# Sheet1.net
KiCad netlist of a schematic drawn in Altium Designer
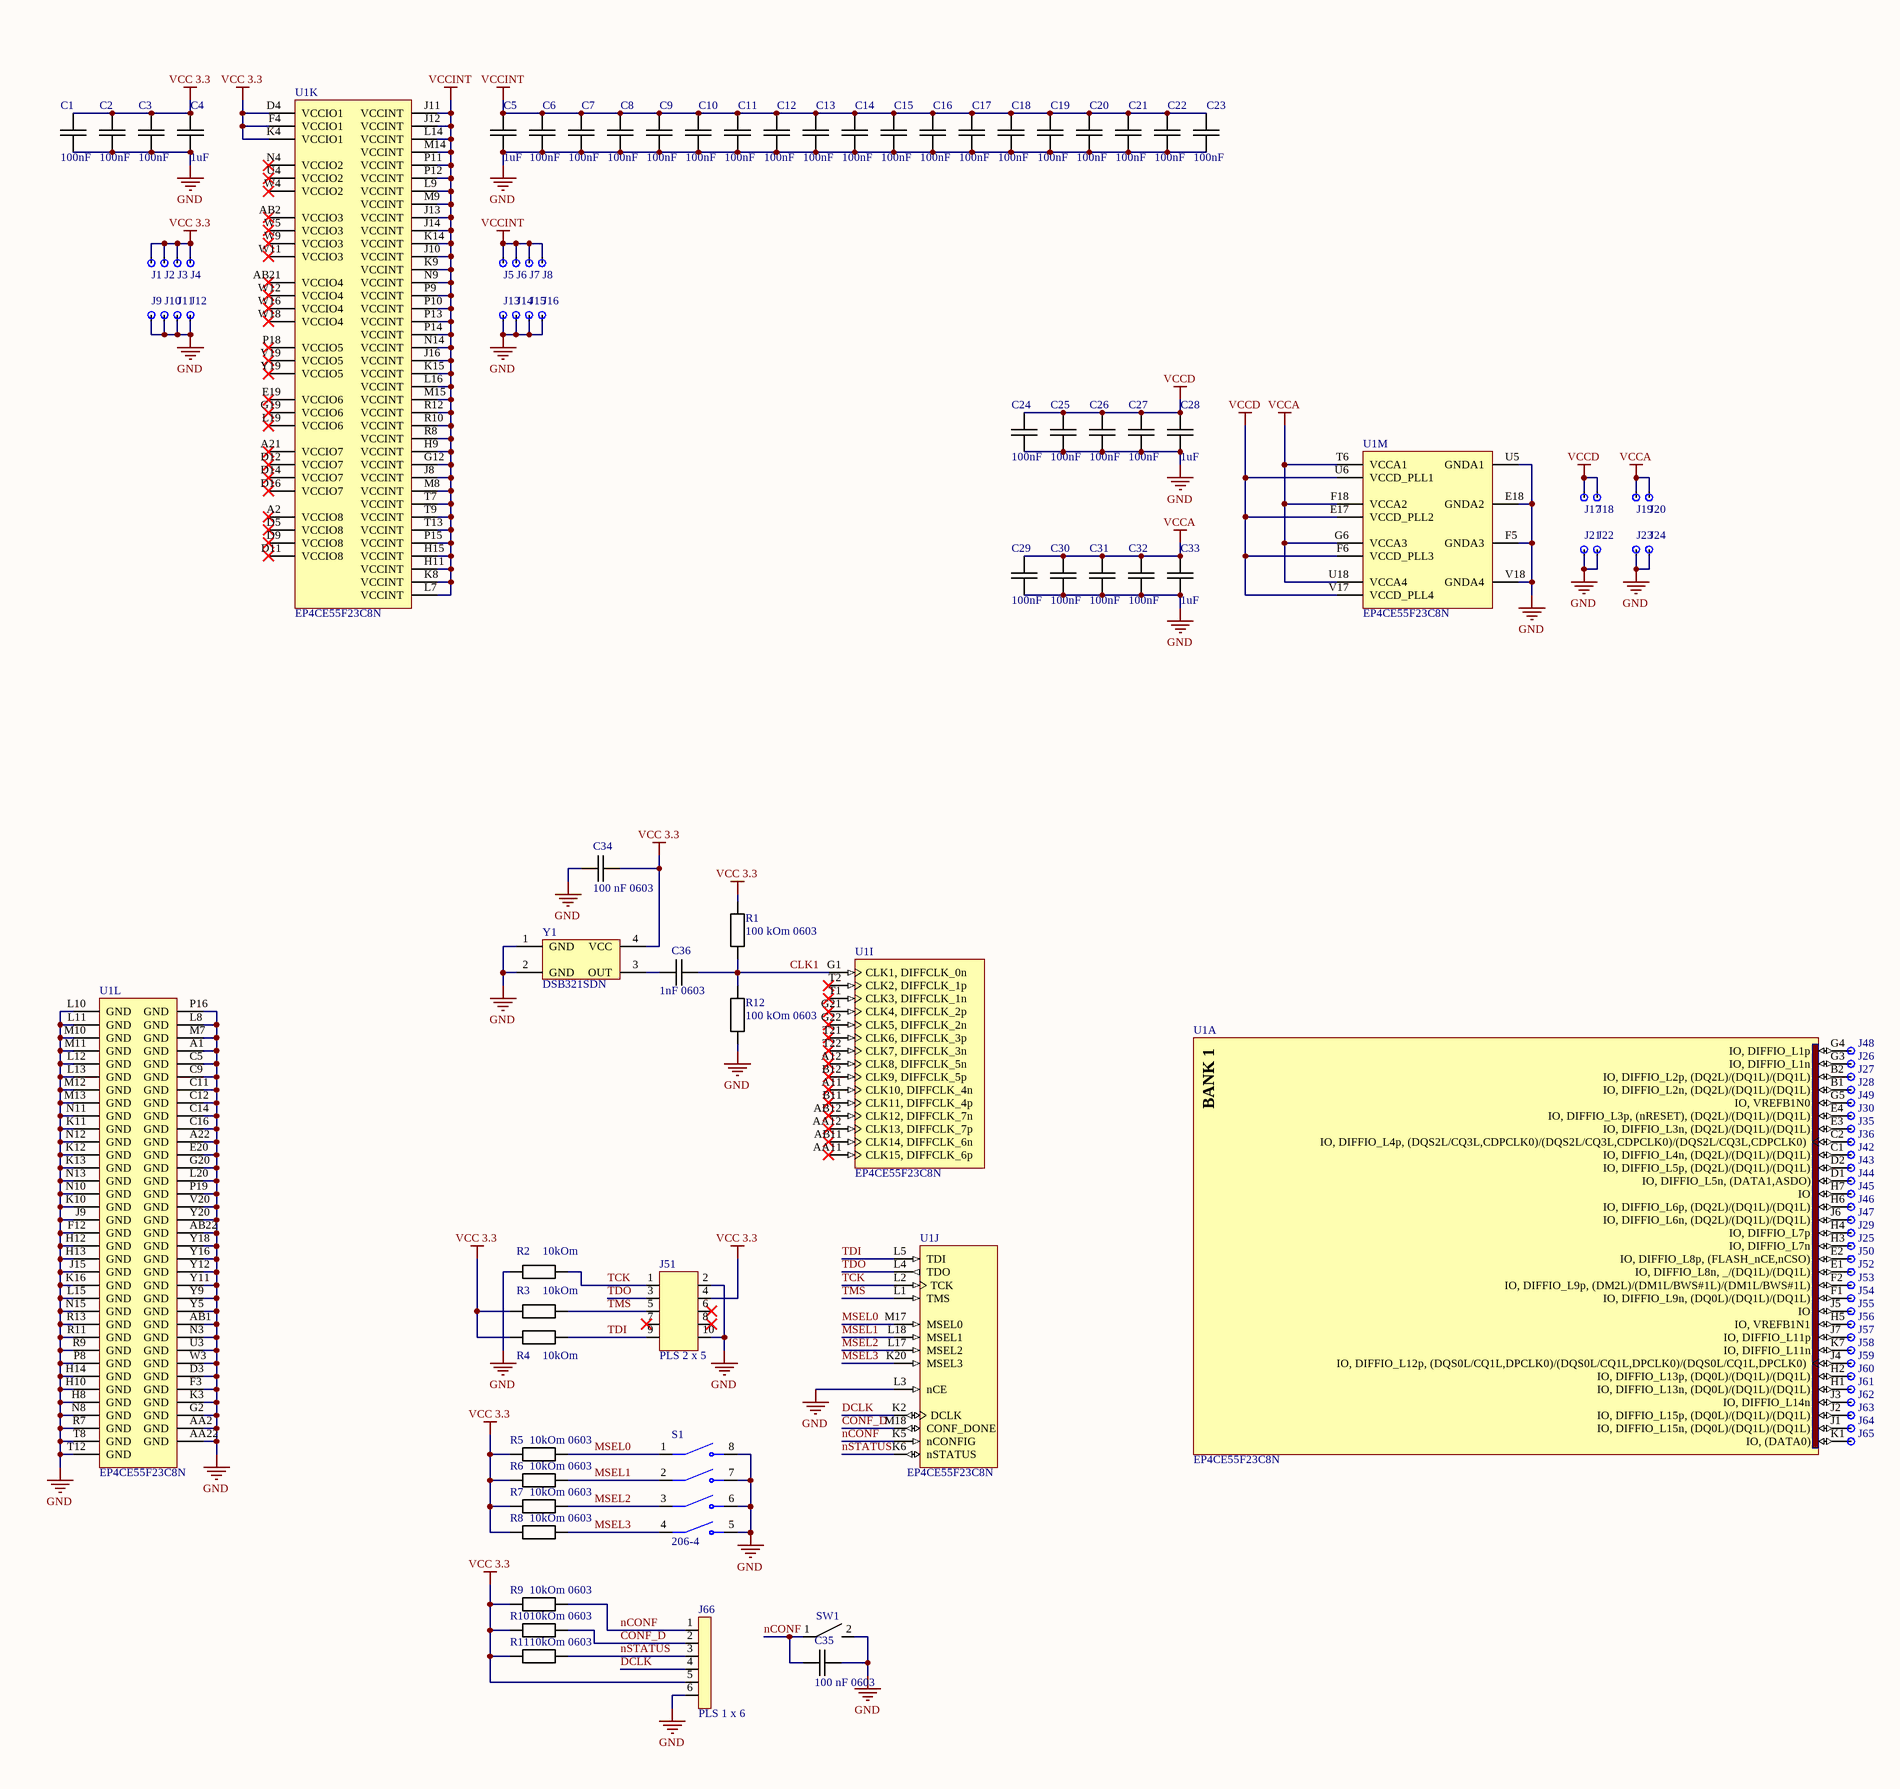
[diagram p0: Sheet1.SchDoc, left]
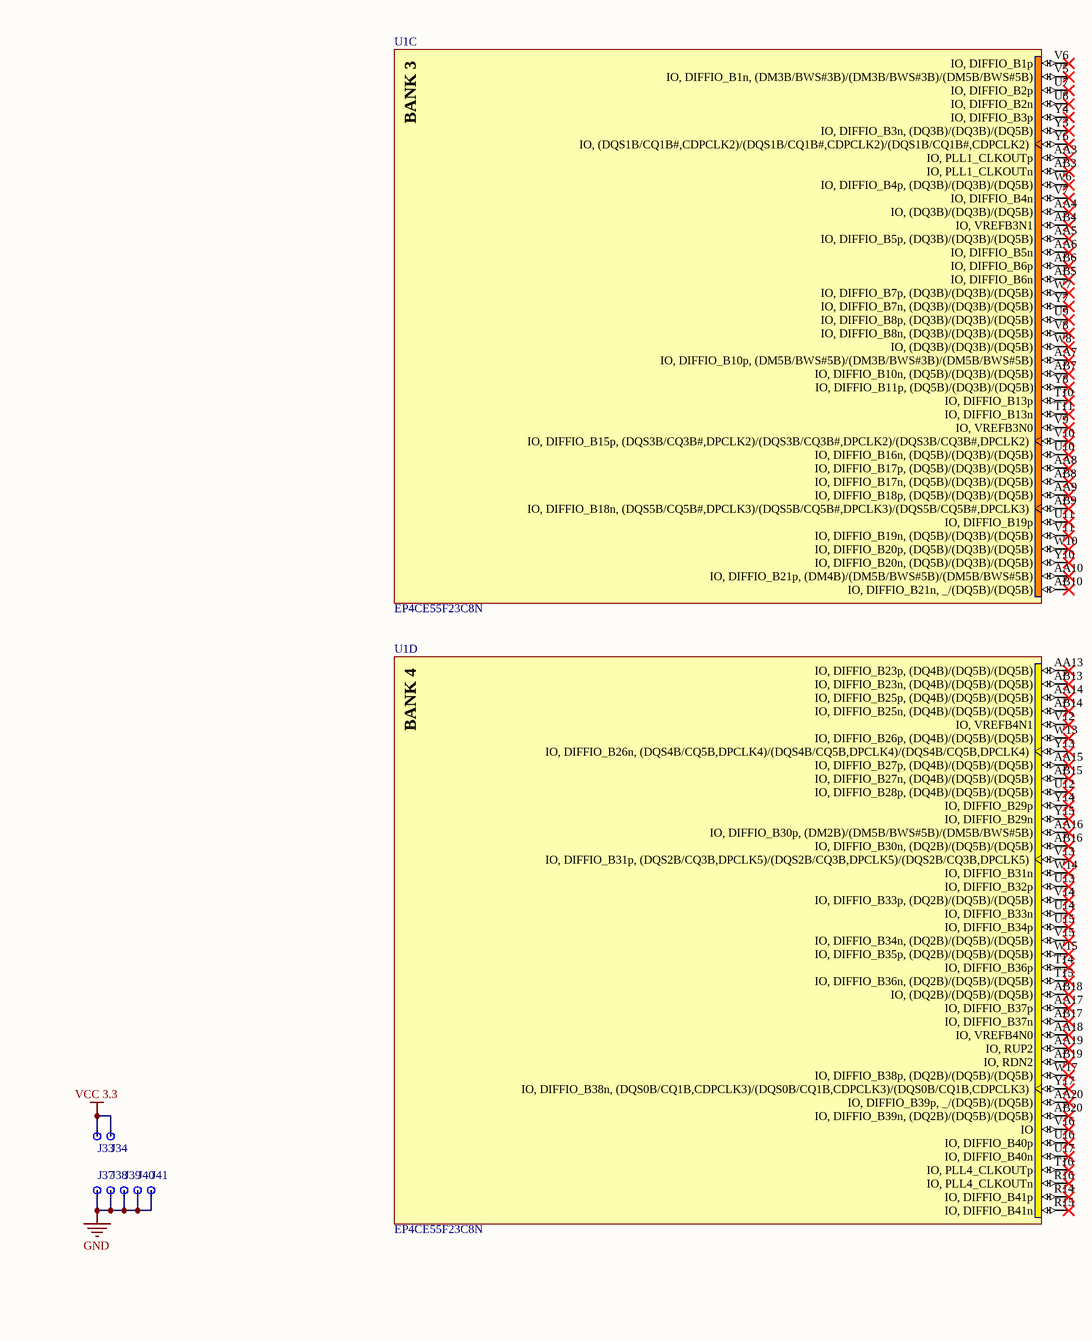
[diagram p1: Sheet1.SchDoc, middle]
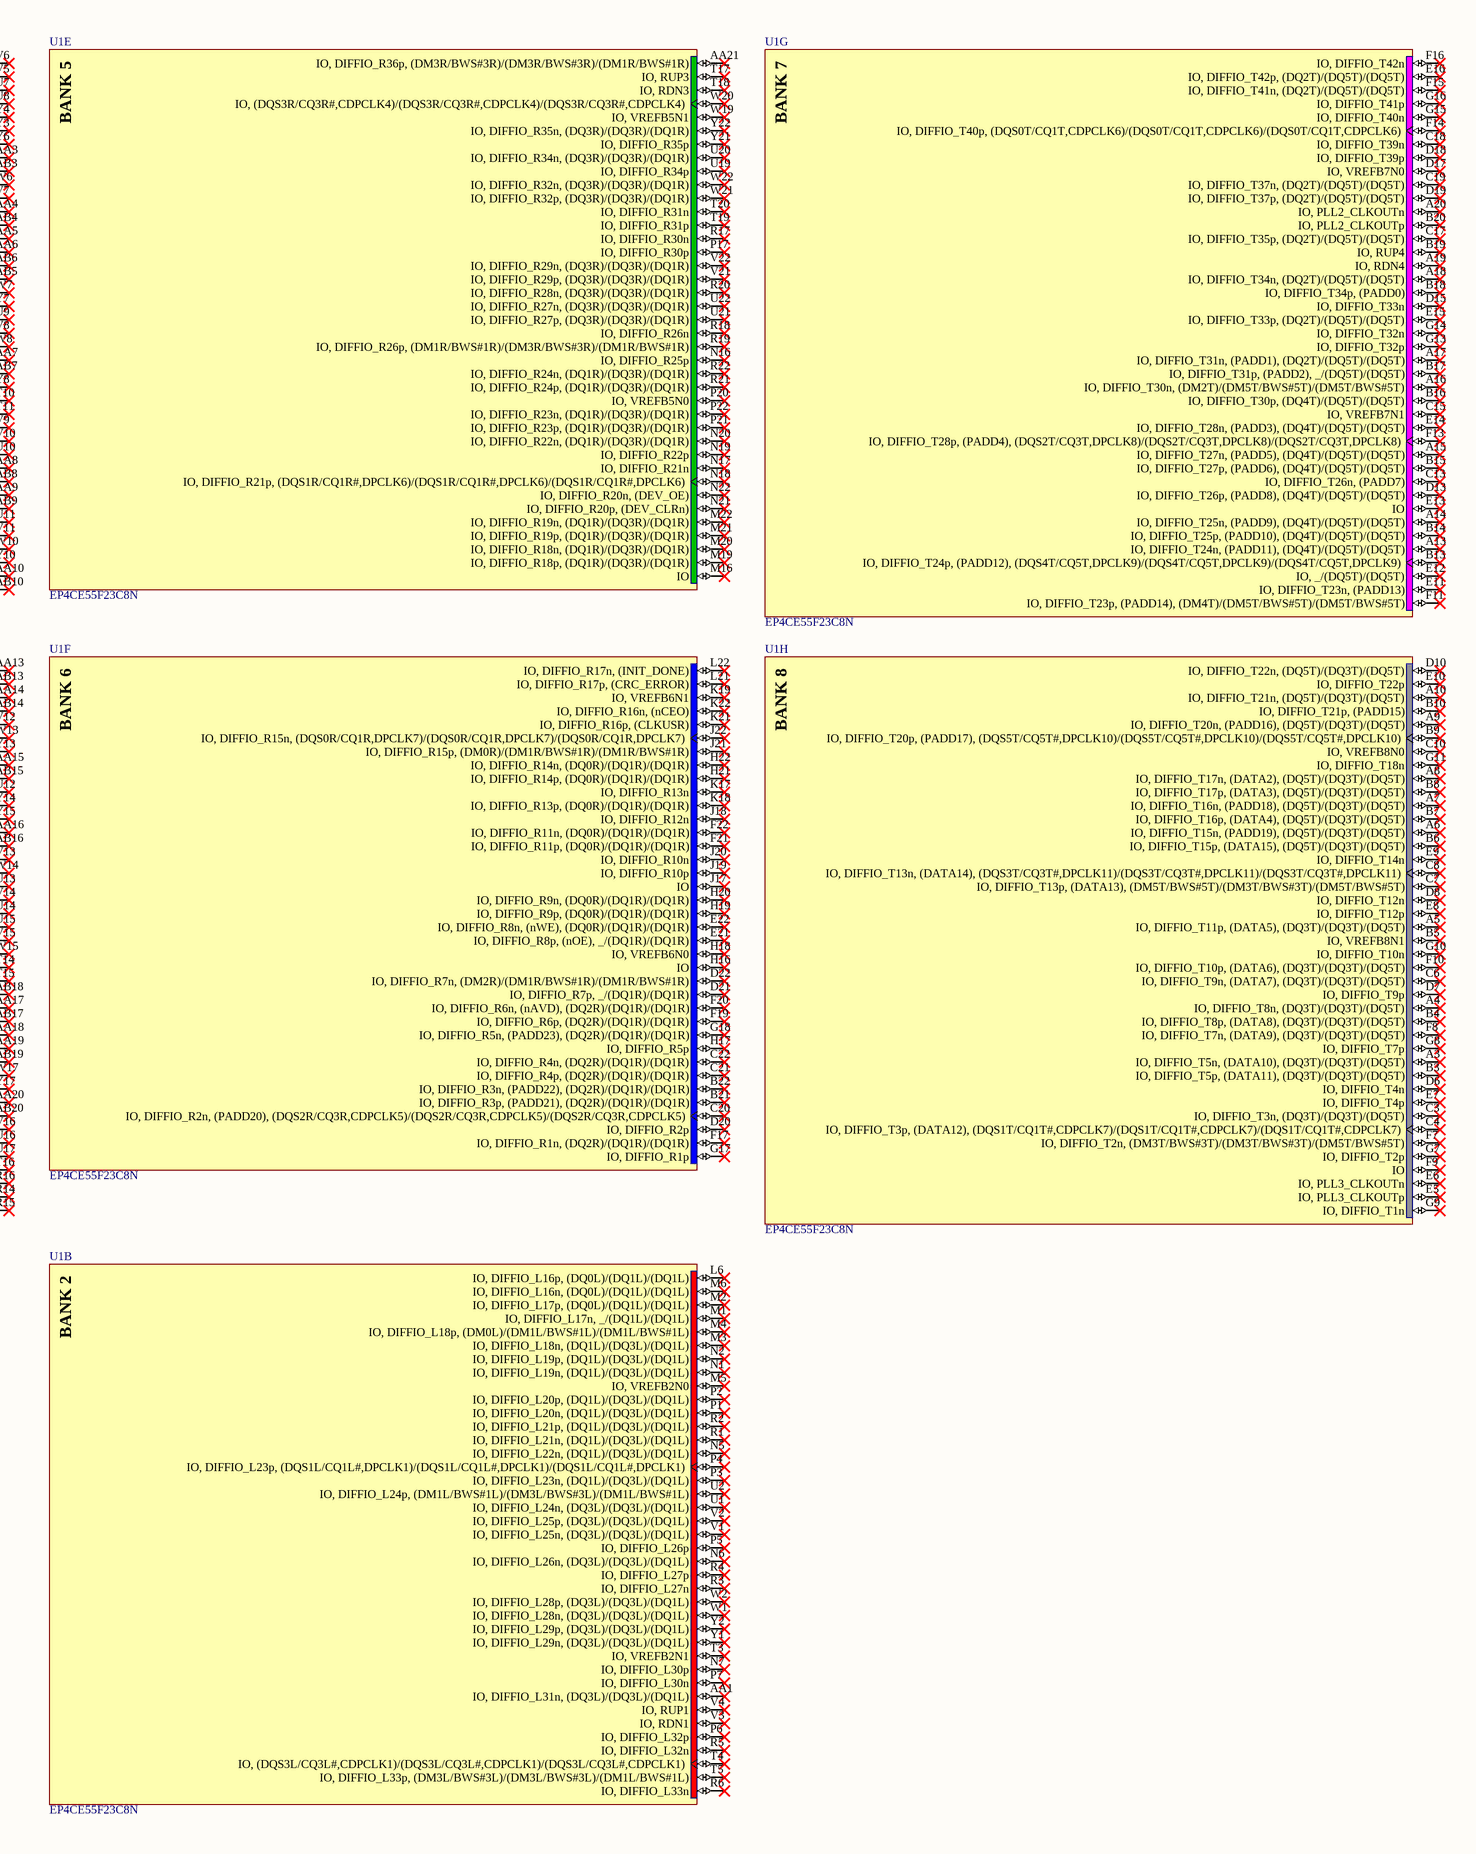
[diagram p2: Sheet1.SchDoc, right]

(export (version "E")
  (design (tool "Eeschema 10.0.6"))
  (components
    (comp (ref "C1")
      (value "100nF")
      (footprint "CAPC1608X90")
      (libsource (lib "Schlib1") (part "100 nF 0603"))
    )
    (comp (ref "C2")
      (value "100nF")
      (footprint "CAPC1608X90")
      (libsource (lib "Schlib1") (part "100 nF 0603"))
    )
    (comp (ref "C3")
      (value "100nF")
      (footprint "CAPC1608X90")
      (libsource (lib "Schlib1") (part "100 nF 0603"))
    )
    (comp (ref "C4") (value "1uF") (footprint "CAPC1608X90") (libsource (lib "Schlib1") (part "1uF 0603")))
    (comp (ref "C5") (value "1uF") (footprint "CAPC1608X90") (libsource (lib "Schlib1") (part "1uF 0603")))
    (comp (ref "C6")
      (value "100nF")
      (footprint "CAPC1608X90")
      (libsource (lib "Schlib1") (part "100 nF 0603"))
    )
    (comp (ref "C7")
      (value "100nF")
      (footprint "CAPC1608X90")
      (libsource (lib "Schlib1") (part "100 nF 0603"))
    )
    (comp (ref "C8")
      (value "100nF")
      (footprint "CAPC1608X90")
      (libsource (lib "Schlib1") (part "100 nF 0603"))
    )
    (comp (ref "C9")
      (value "100nF")
      (footprint "CAPC1608X90")
      (libsource (lib "Schlib1") (part "100 nF 0603"))
    )
    (comp (ref "C10")
      (value "100nF")
      (footprint "CAPC1608X90")
      (libsource (lib "Schlib1") (part "100 nF 0603"))
    )
    (comp (ref "C11")
      (value "100nF")
      (footprint "CAPC1608X90")
      (libsource (lib "Schlib1") (part "100 nF 0603"))
    )
    (comp (ref "C12")
      (value "100nF")
      (footprint "CAPC1608X90")
      (libsource (lib "Schlib1") (part "100 nF 0603"))
    )
    (comp (ref "C13")
      (value "100nF")
      (footprint "CAPC1608X90")
      (libsource (lib "Schlib1") (part "100 nF 0603"))
    )
    (comp (ref "C14")
      (value "100nF")
      (footprint "CAPC1608X90")
      (libsource (lib "Schlib1") (part "100 nF 0603"))
    )
    (comp (ref "C15")
      (value "100nF")
      (footprint "CAPC1608X90")
      (libsource (lib "Schlib1") (part "100 nF 0603"))
    )
    (comp (ref "C16")
      (value "100nF")
      (footprint "CAPC1608X90")
      (libsource (lib "Schlib1") (part "100 nF 0603"))
    )
    (comp (ref "C17")
      (value "100nF")
      (footprint "CAPC1608X90")
      (libsource (lib "Schlib1") (part "100 nF 0603"))
    )
    (comp (ref "C18")
      (value "100nF")
      (footprint "CAPC1608X90")
      (libsource (lib "Schlib1") (part "100 nF 0603"))
    )
    (comp (ref "C19")
      (value "100nF")
      (footprint "CAPC1608X90")
      (libsource (lib "Schlib1") (part "100 nF 0603"))
    )
    (comp (ref "C20")
      (value "100nF")
      (footprint "CAPC1608X90")
      (libsource (lib "Schlib1") (part "100 nF 0603"))
    )
    (comp (ref "C21")
      (value "100nF")
      (footprint "CAPC1608X90")
      (libsource (lib "Schlib1") (part "100 nF 0603"))
    )
    (comp (ref "C22")
      (value "100nF")
      (footprint "CAPC1608X90")
      (libsource (lib "Schlib1") (part "100 nF 0603"))
    )
    (comp (ref "C23")
      (value "100nF")
      (footprint "CAPC1608X90")
      (libsource (lib "Schlib1") (part "100 nF 0603"))
    )
    (comp (ref "C24")
      (value "100nF")
      (footprint "CAPC1608X90")
      (libsource (lib "Schlib1") (part "100 nF 0603"))
    )
    (comp (ref "C25")
      (value "100nF")
      (footprint "CAPC1608X90")
      (libsource (lib "Schlib1") (part "100 nF 0603"))
    )
    (comp (ref "C26")
      (value "100nF")
      (footprint "CAPC1608X90")
      (libsource (lib "Schlib1") (part "100 nF 0603"))
    )
    (comp (ref "C27")
      (value "100nF")
      (footprint "CAPC1608X90")
      (libsource (lib "Schlib1") (part "100 nF 0603"))
    )
    (comp (ref "C28") (value "1uF") (footprint "CAPC1608X90") (libsource (lib "Schlib1") (part "1uF 0603")))
    (comp (ref "C29")
      (value "100nF")
      (footprint "CAPC1608X90")
      (libsource (lib "Schlib1") (part "100 nF 0603"))
    )
    (comp (ref "C30")
      (value "100nF")
      (footprint "CAPC1608X90")
      (libsource (lib "Schlib1") (part "100 nF 0603"))
    )
    (comp (ref "C31")
      (value "100nF")
      (footprint "CAPC1608X90")
      (libsource (lib "Schlib1") (part "100 nF 0603"))
    )
    (comp (ref "C32")
      (value "100nF")
      (footprint "CAPC1608X90")
      (libsource (lib "Schlib1") (part "100 nF 0603"))
    )
    (comp (ref "C33") (value "1uF") (footprint "CAPC1608X90") (libsource (lib "Schlib1") (part "1uF 0603")))
    (comp (ref "C34")
      (value "100 nF 0603")
      (footprint "CAPC1608X90")
      (libsource (lib "Schlib1") (part "100 nF 0603"))
    )
    (comp (ref "C35")
      (value "100 nF 0603")
      (footprint "CAPC1608X90")
      (libsource (lib "Schlib1") (part "100 nF 0603"))
    )
    (comp (ref "C36")
      (value "1nF 0603")
      (footprint "CAPC1608X90")
      (libsource (lib "Schlib1") (part "1nF 0603"))
    )
    (comp (ref "J1") (value "Pin1") (footprint "Pin1") (libsource (lib "Schlib1") (part "Pin1")))
    (comp (ref "J2") (value "Pin1") (footprint "Pin1") (libsource (lib "Schlib1") (part "Pin1")))
    (comp (ref "J3") (value "Pin1") (footprint "Pin1") (libsource (lib "Schlib1") (part "Pin1")))
    (comp (ref "J4") (value "Pin1") (footprint "Pin1") (libsource (lib "Schlib1") (part "Pin1")))
    (comp (ref "J5") (value "Pin1") (footprint "Pin1") (libsource (lib "Schlib1") (part "Pin1")))
    (comp (ref "J6") (value "Pin1") (footprint "Pin1") (libsource (lib "Schlib1") (part "Pin1")))
    (comp (ref "J7") (value "Pin1") (footprint "Pin1") (libsource (lib "Schlib1") (part "Pin1")))
    (comp (ref "J8") (value "Pin1") (footprint "Pin1") (libsource (lib "Schlib1") (part "Pin1")))
    (comp (ref "J9") (value "Pin1") (footprint "Pin1") (libsource (lib "Schlib1") (part "Pin1")))
    (comp (ref "J10") (value "Pin1") (footprint "Pin1") (libsource (lib "Schlib1") (part "Pin1")))
    (comp (ref "J11") (value "Pin1") (footprint "Pin1") (libsource (lib "Schlib1") (part "Pin1")))
    (comp (ref "J12") (value "Pin1") (footprint "Pin1") (libsource (lib "Schlib1") (part "Pin1")))
    (comp (ref "J13") (value "Pin1") (footprint "Pin1") (libsource (lib "Schlib1") (part "Pin1")))
    (comp (ref "J14") (value "Pin1") (footprint "Pin1") (libsource (lib "Schlib1") (part "Pin1")))
    (comp (ref "J15") (value "Pin1") (footprint "Pin1") (libsource (lib "Schlib1") (part "Pin1")))
    (comp (ref "J16") (value "Pin1") (footprint "Pin1") (libsource (lib "Schlib1") (part "Pin1")))
    (comp (ref "J17") (value "Pin1") (footprint "Pin1") (libsource (lib "Schlib1") (part "Pin1")))
    (comp (ref "J18") (value "Pin1") (footprint "Pin1") (libsource (lib "Schlib1") (part "Pin1")))
    (comp (ref "J19") (value "Pin1") (footprint "Pin1") (libsource (lib "Schlib1") (part "Pin1")))
    (comp (ref "J20") (value "Pin1") (footprint "Pin1") (libsource (lib "Schlib1") (part "Pin1")))
    (comp (ref "J21") (value "Pin1") (footprint "Pin1") (libsource (lib "Schlib1") (part "Pin1")))
    (comp (ref "J22") (value "Pin1") (footprint "Pin1") (libsource (lib "Schlib1") (part "Pin1")))
    (comp (ref "J23") (value "Pin1") (footprint "Pin1") (libsource (lib "Schlib1") (part "Pin1")))
    (comp (ref "J24") (value "Pin1") (footprint "Pin1") (libsource (lib "Schlib1") (part "Pin1")))
    (comp (ref "J25") (value "Pin1") (footprint "Pin1") (libsource (lib "Schlib1") (part "Pin1")))
    (comp (ref "J26") (value "Pin1") (footprint "Pin1") (libsource (lib "Schlib1") (part "Pin1")))
    (comp (ref "J27") (value "Pin1") (footprint "Pin1") (libsource (lib "Schlib1") (part "Pin1")))
    (comp (ref "J28") (value "Pin1") (footprint "Pin1") (libsource (lib "Schlib1") (part "Pin1")))
    (comp (ref "J29") (value "Pin1") (footprint "Pin1") (libsource (lib "Schlib1") (part "Pin1")))
    (comp (ref "J30") (value "Pin1") (footprint "Pin1") (libsource (lib "Schlib1") (part "Pin1")))
    (comp (ref "J33") (value "Pin1") (footprint "Pin1") (libsource (lib "Schlib1") (part "Pin1")))
    (comp (ref "J34") (value "Pin1") (footprint "Pin1") (libsource (lib "Schlib1") (part "Pin1")))
    (comp (ref "J35") (value "Pin1") (footprint "Pin1") (libsource (lib "Schlib1") (part "Pin1")))
    (comp (ref "J36") (value "Pin1") (footprint "Pin1") (libsource (lib "Schlib1") (part "Pin1")))
    (comp (ref "J37") (value "Pin1") (footprint "Pin1") (libsource (lib "Schlib1") (part "Pin1")))
    (comp (ref "J38") (value "Pin1") (footprint "Pin1") (libsource (lib "Schlib1") (part "Pin1")))
    (comp (ref "J39") (value "Pin1") (footprint "Pin1") (libsource (lib "Schlib1") (part "Pin1")))
    (comp (ref "J40") (value "Pin1") (footprint "Pin1") (libsource (lib "Schlib1") (part "Pin1")))
    (comp (ref "J41") (value "Pin1") (footprint "Pin1") (libsource (lib "Schlib1") (part "Pin1")))
    (comp (ref "J42") (value "Pin1") (footprint "Pin1") (libsource (lib "Schlib1") (part "Pin1")))
    (comp (ref "J43") (value "Pin1") (footprint "Pin1") (libsource (lib "Schlib1") (part "Pin1")))
    (comp (ref "J44") (value "Pin1") (footprint "Pin1") (libsource (lib "Schlib1") (part "Pin1")))
    (comp (ref "J45") (value "Pin1") (footprint "Pin1") (libsource (lib "Schlib1") (part "Pin1")))
    (comp (ref "J46") (value "Pin1") (footprint "Pin1") (libsource (lib "Schlib1") (part "Pin1")))
    (comp (ref "J47") (value "Pin1") (footprint "Pin1") (libsource (lib "Schlib1") (part "Pin1")))
    (comp (ref "J48") (value "Pin1") (footprint "Pin1") (libsource (lib "Schlib1") (part "Pin1")))
    (comp (ref "J49") (value "Pin1") (footprint "Pin1") (libsource (lib "Schlib1") (part "Pin1")))
    (comp (ref "J50") (value "Pin1") (footprint "Pin1") (libsource (lib "Schlib1") (part "Pin1")))
    (comp (ref "J51")
      (value "PLS 2 x 5")
      (footprint "PLS 2x5 2.54")
      (libsource (lib "Schlib1") (part "PLS 2 x 5"))
    )
    (comp (ref "J52") (value "Pin1") (footprint "Pin1") (libsource (lib "Schlib1") (part "Pin1")))
    (comp (ref "J53") (value "Pin1") (footprint "Pin1") (libsource (lib "Schlib1") (part "Pin1")))
    (comp (ref "J54") (value "Pin1") (footprint "Pin1") (libsource (lib "Schlib1") (part "Pin1")))
    (comp (ref "J55") (value "Pin1") (footprint "Pin1") (libsource (lib "Schlib1") (part "Pin1")))
    (comp (ref "J56") (value "Pin1") (footprint "Pin1") (libsource (lib "Schlib1") (part "Pin1")))
    (comp (ref "J57") (value "Pin1") (footprint "Pin1") (libsource (lib "Schlib1") (part "Pin1")))
    (comp (ref "J58") (value "Pin1") (footprint "Pin1") (libsource (lib "Schlib1") (part "Pin1")))
    (comp (ref "J59") (value "Pin1") (footprint "Pin1") (libsource (lib "Schlib1") (part "Pin1")))
    (comp (ref "J60") (value "Pin1") (footprint "Pin1") (libsource (lib "Schlib1") (part "Pin1")))
    (comp (ref "J61") (value "Pin1") (footprint "Pin1") (libsource (lib "Schlib1") (part "Pin1")))
    (comp (ref "J62") (value "Pin1") (footprint "Pin1") (libsource (lib "Schlib1") (part "Pin1")))
    (comp (ref "J63") (value "Pin1") (footprint "Pin1") (libsource (lib "Schlib1") (part "Pin1")))
    (comp (ref "J64") (value "Pin1") (footprint "Pin1") (libsource (lib "Schlib1") (part "Pin1")))
    (comp (ref "J65") (value "Pin1") (footprint "Pin1") (libsource (lib "Schlib1") (part "Pin1")))
    (comp (ref "J66")
      (value "PLS 1 x 6")
      (footprint "PLS 1x6 2.54")
      (libsource (lib "Schlib1") (part "PLS 1 x 6"))
    )
    (comp (ref "R1")
      (value "100 kOm 0603")
      (footprint "RES 0603")
      (libsource (lib "Schlib1") (part "100 kOm 0603"))
    )
    (comp (ref "R2") (value "10kOm") (footprint "RES 0603") (libsource (lib "Schlib1") (part "10kOm 0603")))
    (comp (ref "R3") (value "10kOm") (footprint "RES 0603") (libsource (lib "Schlib1") (part "10kOm 0603")))
    (comp (ref "R4") (value "10kOm") (footprint "RES 0603") (libsource (lib "Schlib1") (part "10kOm 0603")))
    (comp (ref "R5")
      (value "10kOm 0603")
      (footprint "RES 0603")
      (libsource (lib "Schlib1") (part "10kOm 0603"))
    )
    (comp (ref "R6")
      (value "10kOm 0603")
      (footprint "RES 0603")
      (libsource (lib "Schlib1") (part "10kOm 0603"))
    )
    (comp (ref "R7")
      (value "10kOm 0603")
      (footprint "RES 0603")
      (libsource (lib "Schlib1") (part "10kOm 0603"))
    )
    (comp (ref "R8")
      (value "10kOm 0603")
      (footprint "RES 0603")
      (libsource (lib "Schlib1") (part "10kOm 0603"))
    )
    (comp (ref "R9")
      (value "10kOm 0603")
      (footprint "RES 0603")
      (libsource (lib "Schlib1") (part "10kOm 0603"))
    )
    (comp (ref "R10")
      (value "10kOm 0603")
      (footprint "RES 0603")
      (libsource (lib "Schlib1") (part "10kOm 0603"))
    )
    (comp (ref "R11")
      (value "10kOm 0603")
      (footprint "RES 0603")
      (libsource (lib "Schlib1") (part "10kOm 0603"))
    )
    (comp (ref "R12")
      (value "100 kOm 0603")
      (footprint "RES 0603")
      (libsource (lib "Schlib1") (part "100 kOm 0603"))
    )
    (comp (ref "S1")
      (value "206-4")
      (footprint "SW_206-4")
      (fields (field (name "MF") "{'manufacturer': u'CTS Components'}"))
      (libsource (lib "Schlib1") (part "206-4"))
    )
    (comp (ref "SW1")
      (value "~")
      (footprint "SW_5-1437565-0")
      (description "Alcoswitch, Tactile switch,SMT,SPST,raised actuator ¦ TE Connectivity FSM6JSMATR")
      (fields (field (name "MF") "TE Connectivity") (field (name "MP") "FSM6JSMATR"))
      (libsource (lib "Schlib1") (part "5-1437565-0"))
    )
    (comp (ref "U1")
      (value "EP4CE55F23C8N")
      (footprint "FBGA484_A-240")
      (fields (field (name "MANUFACTURER") "Altera"))
      (libsource (lib "Altium Content Vault") (part "FPGA-ALEP4C-EP4CE55-F484"))
    )
    (comp (ref "Y1")
      (value "DSB321SDN")
      (footprint "DSB321SDN")
      (libsource (lib "Schlib1") (part "DSB321SDN"))
    )
  )
  (nets
    (net (code "1") (name "/CLK1") (class "Default")
      (node (ref "C36") (pin "2") (pinfunction "2_2") (pintype "passive"))
      (node (ref "R1") (pin "1") (pinfunction "1_1") (pintype "passive"))
      (node (ref "R12") (pin "1") (pinfunction "1_1") (pintype "passive"))
      (node (ref "U1") (pin "G1") (pinfunction "CLK1,_DIFFCLK_0n_G1") (pintype "input"))
    )
    (net (code "2") (name "/CONF_D") (class "Default")
      (node (ref "J66") (pin "2") (pinfunction "2_2") (pintype "passive"))
      (node (ref "R10") (pin "1") (pinfunction "1_1") (pintype "passive"))
      (node (ref "U1") (pin "M18") (pinfunction "CONF_DONE_M18") (pintype "bidirectional"))
    )
    (net (code "3") (name "/DCLK") (class "Default")
      (node (ref "J66") (pin "4") (pinfunction "4_4") (pintype "passive"))
      (node (ref "U1") (pin "K2") (pinfunction "DCLK_K2") (pintype "bidirectional"))
    )
    (net (code "4") (name "/MSEL0") (class "Default")
      (node (ref "R5") (pin "1") (pinfunction "1_1") (pintype "passive"))
      (node (ref "S1") (pin "1") (pinfunction "COM1_1") (pintype "passive"))
      (node (ref "U1") (pin "M17") (pinfunction "MSEL0_M17") (pintype "input"))
    )
    (net (code "5") (name "/MSEL1") (class "Default")
      (node (ref "R6") (pin "1") (pinfunction "1_1") (pintype "passive"))
      (node (ref "S1") (pin "2") (pinfunction "COM2_2") (pintype "passive"))
      (node (ref "U1") (pin "L18") (pinfunction "MSEL1_L18") (pintype "input"))
    )
    (net (code "6") (name "/MSEL2") (class "Default")
      (node (ref "R7") (pin "1") (pinfunction "1_1") (pintype "passive"))
      (node (ref "S1") (pin "3") (pinfunction "COM3_3") (pintype "passive"))
      (node (ref "U1") (pin "L17") (pinfunction "MSEL2_L17") (pintype "input"))
    )
    (net (code "7") (name "/MSEL3") (class "Default")
      (node (ref "R8") (pin "1") (pinfunction "1_1") (pintype "passive"))
      (node (ref "S1") (pin "4") (pinfunction "COM4_4") (pintype "passive"))
      (node (ref "U1") (pin "K20") (pinfunction "MSEL3_K20") (pintype "input"))
    )
    (net (code "8") (name "/TCK") (class "Default")
      (node (ref "J51") (pin "1") (pinfunction "1_1") (pintype "passive"))
      (node (ref "R2") (pin "2") (pinfunction "2_2") (pintype "passive"))
      (node (ref "U1") (pin "L2") (pinfunction "TCK_L2") (pintype "input"))
    )
    (net (code "9") (name "/TDI") (class "Default")
      (node (ref "J51") (pin "9") (pinfunction "9_9") (pintype "passive"))
      (node (ref "R4") (pin "1") (pinfunction "1_1") (pintype "passive"))
      (node (ref "U1") (pin "L5") (pinfunction "TDI_L5") (pintype "input"))
    )
    (net (code "10") (name "/TDO") (class "Default")
      (node (ref "J51") (pin "3") (pinfunction "3_3") (pintype "passive"))
      (node (ref "U1") (pin "L4") (pinfunction "TDO_L4") (pintype "output"))
    )
    (net (code "11") (name "/TMS") (class "Default")
      (node (ref "J51") (pin "5") (pinfunction "5_5") (pintype "passive"))
      (node (ref "R3") (pin "1") (pinfunction "1_1") (pintype "passive"))
      (node (ref "U1") (pin "L1") (pinfunction "TMS_L1") (pintype "input"))
    )
    (net (code "12") (name "/nCONF") (class "Default")
      (node (ref "C35") (pin "1") (pinfunction "1_1") (pintype "passive"))
      (node (ref "J66") (pin "1") (pinfunction "1_1") (pintype "passive"))
      (node (ref "R9") (pin "1") (pinfunction "1_1") (pintype "passive"))
      (node (ref "SW1") (pin "1") (pinfunction "2_1") (pintype "passive"))
      (node (ref "U1") (pin "K5") (pinfunction "nCONFIG_K5") (pintype "input"))
    )
    (net (code "13") (name "/nSTATUS") (class "Default")
      (node (ref "J66") (pin "3") (pinfunction "3_3") (pintype "passive"))
      (node (ref "R11") (pin "1") (pinfunction "1_1") (pintype "passive"))
      (node (ref "U1") (pin "K6") (pinfunction "nSTATUS_K6") (pintype "bidirectional"))
    )
    (net (code "14") (name "GND") (class "Default")
      (node (ref "C1") (pin "1") (pinfunction "1_1") (pintype "passive"))
      (node (ref "C10") (pin "1") (pinfunction "1_1") (pintype "passive"))
      (node (ref "C11") (pin "1") (pinfunction "1_1") (pintype "passive"))
      (node (ref "C12") (pin "1") (pinfunction "1_1") (pintype "passive"))
      (node (ref "C13") (pin "1") (pinfunction "1_1") (pintype "passive"))
      (node (ref "C14") (pin "1") (pinfunction "1_1") (pintype "passive"))
      (node (ref "C15") (pin "1") (pinfunction "1_1") (pintype "passive"))
      (node (ref "C16") (pin "1") (pinfunction "1_1") (pintype "passive"))
      (node (ref "C17") (pin "1") (pinfunction "1_1") (pintype "passive"))
      (node (ref "C18") (pin "1") (pinfunction "1_1") (pintype "passive"))
      (node (ref "C19") (pin "1") (pinfunction "1_1") (pintype "passive"))
      (node (ref "C2") (pin "1") (pinfunction "1_1") (pintype "passive"))
      (node (ref "C20") (pin "1") (pinfunction "1_1") (pintype "passive"))
      (node (ref "C21") (pin "1") (pinfunction "1_1") (pintype "passive"))
      (node (ref "C22") (pin "1") (pinfunction "1_1") (pintype "passive"))
      (node (ref "C23") (pin "1") (pinfunction "1_1") (pintype "passive"))
      (node (ref "C24") (pin "1") (pinfunction "1_1") (pintype "passive"))
      (node (ref "C25") (pin "1") (pinfunction "1_1") (pintype "passive"))
      (node (ref "C26") (pin "1") (pinfunction "1_1") (pintype "passive"))
      (node (ref "C27") (pin "1") (pinfunction "1_1") (pintype "passive"))
      (node (ref "C28") (pin "1") (pinfunction "1_1") (pintype "passive"))
      (node (ref "C29") (pin "1") (pinfunction "1_1") (pintype "passive"))
      (node (ref "C3") (pin "1") (pinfunction "1_1") (pintype "passive"))
      (node (ref "C30") (pin "1") (pinfunction "1_1") (pintype "passive"))
      (node (ref "C31") (pin "1") (pinfunction "1_1") (pintype "passive"))
      (node (ref "C32") (pin "1") (pinfunction "1_1") (pintype "passive"))
      (node (ref "C33") (pin "1") (pinfunction "1_1") (pintype "passive"))
      (node (ref "C34") (pin "1") (pinfunction "1_1") (pintype "passive"))
      (node (ref "C35") (pin "2") (pinfunction "2_2") (pintype "passive"))
      (node (ref "C4") (pin "1") (pinfunction "1_1") (pintype "passive"))
      (node (ref "C5") (pin "1") (pinfunction "1_1") (pintype "passive"))
      (node (ref "C6") (pin "1") (pinfunction "1_1") (pintype "passive"))
      (node (ref "C7") (pin "1") (pinfunction "1_1") (pintype "passive"))
      (node (ref "C8") (pin "1") (pinfunction "1_1") (pintype "passive"))
      (node (ref "C9") (pin "1") (pinfunction "1_1") (pintype "passive"))
      (node (ref "J10") (pin "1") (pinfunction "1_1") (pintype "passive"))
      (node (ref "J11") (pin "1") (pinfunction "1_1") (pintype "passive"))
      (node (ref "J12") (pin "1") (pinfunction "1_1") (pintype "passive"))
      (node (ref "J13") (pin "1") (pinfunction "1_1") (pintype "passive"))
      (node (ref "J14") (pin "1") (pinfunction "1_1") (pintype "passive"))
      (node (ref "J15") (pin "1") (pinfunction "1_1") (pintype "passive"))
      (node (ref "J16") (pin "1") (pinfunction "1_1") (pintype "passive"))
      (node (ref "J21") (pin "1") (pinfunction "1_1") (pintype "passive"))
      (node (ref "J22") (pin "1") (pinfunction "1_1") (pintype "passive"))
      (node (ref "J23") (pin "1") (pinfunction "1_1") (pintype "passive"))
      (node (ref "J24") (pin "1") (pinfunction "1_1") (pintype "passive"))
      (node (ref "J37") (pin "1") (pinfunction "1_1") (pintype "passive"))
      (node (ref "J38") (pin "1") (pinfunction "1_1") (pintype "passive"))
      (node (ref "J39") (pin "1") (pinfunction "1_1") (pintype "passive"))
      (node (ref "J40") (pin "1") (pinfunction "1_1") (pintype "passive"))
      (node (ref "J41") (pin "1") (pinfunction "1_1") (pintype "passive"))
      (node (ref "J51") (pin "10") (pinfunction "10_10") (pintype "passive"))
      (node (ref "J51") (pin "2") (pinfunction "2_2") (pintype "passive"))
      (node (ref "J66") (pin "6") (pinfunction "6_6") (pintype "passive"))
      (node (ref "J9") (pin "1") (pinfunction "1_1") (pintype "passive"))
      (node (ref "R12") (pin "2") (pinfunction "2_2") (pintype "passive"))
      (node (ref "R2") (pin "1") (pinfunction "1_1") (pintype "passive"))
      (node (ref "S1") (pin "5") (pinfunction "NO4_5") (pintype "passive"))
      (node (ref "S1") (pin "6") (pinfunction "NO3_6") (pintype "passive"))
      (node (ref "S1") (pin "7") (pinfunction "NO2_7") (pintype "passive"))
      (node (ref "S1") (pin "8") (pinfunction "NO1_8") (pintype "passive"))
      (node (ref "SW1") (pin "2") (pinfunction "2_2") (pintype "passive"))
      (node (ref "U1") (pin "A1") (pinfunction "GND_A1") (pintype "power_in"))
      (node (ref "U1") (pin "A22") (pinfunction "GND_A22") (pintype "power_in"))
      (node (ref "U1") (pin "AA2") (pinfunction "GND_AA2") (pintype "power_in"))
      (node (ref "U1") (pin "AA22") (pinfunction "GND_AA22") (pintype "power_in"))
      (node (ref "U1") (pin "AB1") (pinfunction "GND_AB1") (pintype "power_in"))
      (node (ref "U1") (pin "AB22") (pinfunction "GND_AB22") (pintype "power_in"))
      (node (ref "U1") (pin "C11") (pinfunction "GND_C11") (pintype "power_in"))
      (node (ref "U1") (pin "C12") (pinfunction "GND_C12") (pintype "power_in"))
      (node (ref "U1") (pin "C14") (pinfunction "GND_C14") (pintype "power_in"))
      (node (ref "U1") (pin "C16") (pinfunction "GND_C16") (pintype "power_in"))
      (node (ref "U1") (pin "C5") (pinfunction "GND_C5") (pintype "power_in"))
      (node (ref "U1") (pin "C9") (pinfunction "GND_C9") (pintype "power_in"))
      (node (ref "U1") (pin "D3") (pinfunction "GND_D3") (pintype "power_in"))
      (node (ref "U1") (pin "E18") (pinfunction "GNDA2_E18") (pintype "power_in"))
      (node (ref "U1") (pin "E20") (pinfunction "GND_E20") (pintype "power_in"))
      (node (ref "U1") (pin "F12") (pinfunction "GND_F12") (pintype "power_in"))
      (node (ref "U1") (pin "F3") (pinfunction "GND_F3") (pintype "power_in"))
      (node (ref "U1") (pin "F5") (pinfunction "GNDA3_F5") (pintype "power_in"))
      (node (ref "U1") (pin "G2") (pinfunction "GND_G2") (pintype "power_in"))
      (node (ref "U1") (pin "G20") (pinfunction "GND_G20") (pintype "power_in"))
      (node (ref "U1") (pin "H10") (pinfunction "GND_H10") (pintype "power_in"))
      (node (ref "U1") (pin "H12") (pinfunction "GND_H12") (pintype "power_in"))
      (node (ref "U1") (pin "H13") (pinfunction "GND_H13") (pintype "power_in"))
      (node (ref "U1") (pin "H14") (pinfunction "GND_H14") (pintype "power_in"))
      (node (ref "U1") (pin "H8") (pinfunction "GND_H8") (pintype "power_in"))
      (node (ref "U1") (pin "J15") (pinfunction "GND_J15") (pintype "power_in"))
      (node (ref "U1") (pin "J9") (pinfunction "GND_J9") (pintype "power_in"))
      (node (ref "U1") (pin "K10") (pinfunction "GND_K10") (pintype "power_in"))
      (node (ref "U1") (pin "K11") (pinfunction "GND_K11") (pintype "power_in"))
      (node (ref "U1") (pin "K12") (pinfunction "GND_K12") (pintype "power_in"))
      (node (ref "U1") (pin "K13") (pinfunction "GND_K13") (pintype "power_in"))
      (node (ref "U1") (pin "K16") (pinfunction "GND_K16") (pintype "power_in"))
      (node (ref "U1") (pin "K3") (pinfunction "GND_K3") (pintype "power_in"))
      (node (ref "U1") (pin "L10") (pinfunction "GND_L10") (pintype "power_in"))
      (node (ref "U1") (pin "L11") (pinfunction "GND_L11") (pintype "power_in"))
      (node (ref "U1") (pin "L12") (pinfunction "GND_L12") (pintype "power_in"))
      (node (ref "U1") (pin "L13") (pinfunction "GND_L13") (pintype "power_in"))
      (node (ref "U1") (pin "L15") (pinfunction "GND_L15") (pintype "power_in"))
      (node (ref "U1") (pin "L20") (pinfunction "GND_L20") (pintype "power_in"))
      (node (ref "U1") (pin "L3") (pinfunction "nCE_L3") (pintype "input"))
      (node (ref "U1") (pin "L8") (pinfunction "GND_L8") (pintype "power_in"))
      (node (ref "U1") (pin "M10") (pinfunction "GND_M10") (pintype "power_in"))
      (node (ref "U1") (pin "M11") (pinfunction "GND_M11") (pintype "power_in"))
      (node (ref "U1") (pin "M12") (pinfunction "GND_M12") (pintype "power_in"))
      (node (ref "U1") (pin "M13") (pinfunction "GND_M13") (pintype "power_in"))
      (node (ref "U1") (pin "M7") (pinfunction "GND_M7") (pintype "power_in"))
      (node (ref "U1") (pin "N10") (pinfunction "GND_N10") (pintype "power_in"))
      (node (ref "U1") (pin "N11") (pinfunction "GND_N11") (pintype "power_in"))
      (node (ref "U1") (pin "N12") (pinfunction "GND_N12") (pintype "power_in"))
      (node (ref "U1") (pin "N13") (pinfunction "GND_N13") (pintype "power_in"))
      (node (ref "U1") (pin "N15") (pinfunction "GND_N15") (pintype "power_in"))
      (node (ref "U1") (pin "N3") (pinfunction "GND_N3") (pintype "power_in"))
      (node (ref "U1") (pin "N8") (pinfunction "GND_N8") (pintype "power_in"))
      (node (ref "U1") (pin "P16") (pinfunction "GND_P16") (pintype "power_in"))
      (node (ref "U1") (pin "P19") (pinfunction "GND_P19") (pintype "power_in"))
      (node (ref "U1") (pin "P8") (pinfunction "GND_P8") (pintype "power_in"))
      (node (ref "U1") (pin "R11") (pinfunction "GND_R11") (pintype "power_in"))
      (node (ref "U1") (pin "R13") (pinfunction "GND_R13") (pintype "power_in"))
      (node (ref "U1") (pin "R7") (pinfunction "GND_R7") (pintype "power_in"))
      (node (ref "U1") (pin "R9") (pinfunction "GND_R9") (pintype "power_in"))
      (node (ref "U1") (pin "T12") (pinfunction "GND_T12") (pintype "power_in"))
      (node (ref "U1") (pin "T8") (pinfunction "GND_T8") (pintype "power_in"))
      (node (ref "U1") (pin "U3") (pinfunction "GND_U3") (pintype "power_in"))
      (node (ref "U1") (pin "U5") (pinfunction "GNDA1_U5") (pintype "power_in"))
      (node (ref "U1") (pin "V18") (pinfunction "GNDA4_V18") (pintype "power_in"))
      (node (ref "U1") (pin "V20") (pinfunction "GND_V20") (pintype "power_in"))
      (node (ref "U1") (pin "W3") (pinfunction "GND_W3") (pintype "power_in"))
      (node (ref "U1") (pin "Y11") (pinfunction "GND_Y11") (pintype "power_in"))
      (node (ref "U1") (pin "Y12") (pinfunction "GND_Y12") (pintype "power_in"))
      (node (ref "U1") (pin "Y16") (pinfunction "GND_Y16") (pintype "power_in"))
      (node (ref "U1") (pin "Y18") (pinfunction "GND_Y18") (pintype "power_in"))
      (node (ref "U1") (pin "Y20") (pinfunction "GND_Y20") (pintype "power_in"))
      (node (ref "U1") (pin "Y5") (pinfunction "GND_Y5") (pintype "power_in"))
      (node (ref "U1") (pin "Y9") (pinfunction "GND_Y9") (pintype "power_in"))
      (node (ref "Y1") (pin "1") (pinfunction "GND_1") (pintype "passive"))
      (node (ref "Y1") (pin "2") (pinfunction "GND_2") (pintype "passive"))
    )
    (net (code "15") (name "Net-(J45-Pad1)") (class "Default")
      (node (ref "J45") (pin "1") (pinfunction "1_1") (pintype "passive"))
      (node (ref "U1") (pin "H7") (pinfunction "IO_H7") (pintype "bidirectional"))
    )
    (net (code "16") (name "Net-(J55-Pad1)") (class "Default")
      (node (ref "J55") (pin "1") (pinfunction "1_1") (pintype "passive"))
      (node (ref "U1") (pin "J5") (pinfunction "IO_J5") (pintype "bidirectional"))
    )
    (net (code "17") (name "Net-(U1A-IO,_(DATA0))") (class "Default")
      (node (ref "J65") (pin "1") (pinfunction "1_1") (pintype "passive"))
      (node (ref "U1") (pin "K1") (pinfunction "IO,_(DATA0)_K1") (pintype "bidirectional"))
    )
    (net (code "18") (name "Net-(U1A-IO,_DIFFIO_L1n)") (class "Default")
      (node (ref "J26") (pin "1") (pinfunction "1_1") (pintype "passive"))
      (node (ref "U1") (pin "G3") (pinfunction "IO,_DIFFIO_L1n_G3") (pintype "bidirectional"))
    )
    (net (code "19") (name "Net-(U1A-IO,_DIFFIO_L1p)") (class "Default")
      (node (ref "J48") (pin "1") (pinfunction "1_1") (pintype "passive"))
      (node (ref "U1") (pin "G4") (pinfunction "IO,_DIFFIO_L1p_G4") (pintype "bidirectional"))
    )
    (net (code "20") (name "Net-(U1A-IO,_DIFFIO_L2n,_(DQ2L){slash}(DQ1L){slash}(DQ1L))") (class "Default")
      (node (ref "J28") (pin "1") (pinfunction "1_1") (pintype "passive"))
      (node (ref "U1") (pin "B1") (pinfunction "IO,_DIFFIO_L2n,_(DQ2L)/(DQ1L)/(DQ1L)_B1") (pintype "bidirectional"))
    )
    (net (code "21") (name "Net-(U1A-IO,_DIFFIO_L2p,_(DQ2L){slash}(DQ1L){slash}(DQ1L))") (class "Default")
      (node (ref "J27") (pin "1") (pinfunction "1_1") (pintype "passive"))
      (node (ref "U1") (pin "B2") (pinfunction "IO,_DIFFIO_L2p,_(DQ2L)/(DQ1L)/(DQ1L)_B2") (pintype "bidirectional"))
    )
    (net (code "22") (name "Net-(U1A-IO,_DIFFIO_L3n,_(DQ2L){slash}(DQ1L){slash}(DQ1L))") (class "Default")
      (node (ref "J35") (pin "1") (pinfunction "1_1") (pintype "passive"))
      (node (ref "U1") (pin "E3") (pinfunction "IO,_DIFFIO_L3n,_(DQ2L)/(DQ1L)/(DQ1L)_E3") (pintype "bidirectional"))
    )
    (net (code "23") (name "Net-(U1A-IO,_DIFFIO_L3p,_(nRESET),_(DQ2L){slash}(DQ1L){slash}(DQ1L))") (class "Default")
      (node (ref "J30") (pin "1") (pinfunction "1_1") (pintype "passive"))
      (node (ref "U1") (pin "E4") (pinfunction "IO,_DIFFIO_L3p,_(nRESET),_(DQ2L)/(DQ1L)/(DQ1L)_E4") (pintype "bidirectional"))
    )
    (net (code "24") (name "Net-(U1A-IO,_DIFFIO_L4n,_(DQ2L){slash}(DQ1L){slash}(DQ1L))") (class "Default")
      (node (ref "J42") (pin "1") (pinfunction "1_1") (pintype "passive"))
      (node (ref "U1") (pin "C1") (pinfunction "IO,_DIFFIO_L4n,_(DQ2L)/(DQ1L)/(DQ1L)_C1") (pintype "bidirectional"))
    )
    (net (code "25") (name "Net-(U1A-IO,_DIFFIO_L4p,_(DQS2L{slash}CQ3L,CDPCLK0){slash}(DQS2L{slash}CQ3L,CDPCLK0){slash}(DQS2L{slash}CQ3L,CDPCLK0))") (class "Default")
      (node (ref "J36") (pin "1") (pinfunction "1_1") (pintype "passive"))
      (node (ref "U1") (pin "C2") (pinfunction "IO,_DIFFIO_L4p,_(DQS2L/CQ3L,CDPCLK0)/(DQS2L/CQ3L,CDPCLK0)/(DQS2L/CQ3L,CDPCLK0)_C2") (pintype "bidirectional"))
    )
    (net (code "26") (name "Net-(U1A-IO,_DIFFIO_L5n,_(DATA1,ASDO))") (class "Default")
      (node (ref "J44") (pin "1") (pinfunction "1_1") (pintype "passive"))
      (node (ref "U1") (pin "D1") (pinfunction "IO,_DIFFIO_L5n,_(DATA1,ASDO)_D1") (pintype "bidirectional"))
    )
    (net (code "27") (name "Net-(U1A-IO,_DIFFIO_L5p,_(DQ2L){slash}(DQ1L){slash}(DQ1L))") (class "Default")
      (node (ref "J43") (pin "1") (pinfunction "1_1") (pintype "passive"))
      (node (ref "U1") (pin "D2") (pinfunction "IO,_DIFFIO_L5p,_(DQ2L)/(DQ1L)/(DQ1L)_D2") (pintype "bidirectional"))
    )
    (net (code "28") (name "Net-(U1A-IO,_DIFFIO_L6n,_(DQ2L){slash}(DQ1L){slash}(DQ1L))") (class "Default")
      (node (ref "J47") (pin "1") (pinfunction "1_1") (pintype "passive"))
      (node (ref "U1") (pin "J6") (pinfunction "IO,_DIFFIO_L6n,_(DQ2L)/(DQ1L)/(DQ1L)_J6") (pintype "bidirectional"))
    )
    (net (code "29") (name "Net-(U1A-IO,_DIFFIO_L6p,_(DQ2L){slash}(DQ1L){slash}(DQ1L))") (class "Default")
      (node (ref "J46") (pin "1") (pinfunction "1_1") (pintype "passive"))
      (node (ref "U1") (pin "H6") (pinfunction "IO,_DIFFIO_L6p,_(DQ2L)/(DQ1L)/(DQ1L)_H6") (pintype "bidirectional"))
    )
    (net (code "30") (name "Net-(U1A-IO,_DIFFIO_L7n)") (class "Default")
      (node (ref "J25") (pin "1") (pinfunction "1_1") (pintype "passive"))
      (node (ref "U1") (pin "H3") (pinfunction "IO,_DIFFIO_L7n_H3") (pintype "bidirectional"))
    )
    (net (code "31") (name "Net-(U1A-IO,_DIFFIO_L7p)") (class "Default")
      (node (ref "J29") (pin "1") (pinfunction "1_1") (pintype "passive"))
      (node (ref "U1") (pin "H4") (pinfunction "IO,_DIFFIO_L7p_H4") (pintype "bidirectional"))
    )
    (net (code "32") (name "Net-(U1A-IO,_DIFFIO_L8n,__{slash}(DQ1L){slash}(DQ1L))") (class "Default")
      (node (ref "J52") (pin "1") (pinfunction "1_1") (pintype "passive"))
      (node (ref "U1") (pin "E1") (pinfunction "IO,_DIFFIO_L8n,__/(DQ1L)/(DQ1L)_E1") (pintype "bidirectional"))
    )
    (net (code "33") (name "Net-(U1A-IO,_DIFFIO_L8p,_(FLASH_nCE,nCSO))") (class "Default")
      (node (ref "J50") (pin "1") (pinfunction "1_1") (pintype "passive"))
      (node (ref "U1") (pin "E2") (pinfunction "IO,_DIFFIO_L8p,_(FLASH_nCE,nCSO)_E2") (pintype "bidirectional"))
    )
    (net (code "34") (name "Net-(U1A-IO,_DIFFIO_L9n,_(DQ0L){slash}(DQ1L){slash}(DQ1L))") (class "Default")
      (node (ref "J54") (pin "1") (pinfunction "1_1") (pintype "passive"))
      (node (ref "U1") (pin "F1") (pinfunction "IO,_DIFFIO_L9n,_(DQ0L)/(DQ1L)/(DQ1L)_F1") (pintype "bidirectional"))
    )
    (net (code "35") (name "Net-(U1A-IO,_DIFFIO_L9p,_(DM2L){slash}(DM1L{slash}BWS#1L){slash}(DM1L{slash}BWS#1L))") (class "Default")
      (node (ref "J53") (pin "1") (pinfunction "1_1") (pintype "passive"))
      (node (ref "U1") (pin "F2") (pinfunction "IO,_DIFFIO_L9p,_(DM2L)/(DM1L/BWS#1L)/(DM1L/BWS#1L)_F2") (pintype "bidirectional"))
    )
    (net (code "36") (name "Net-(U1A-IO,_DIFFIO_L11n)") (class "Default")
      (node (ref "J58") (pin "1") (pinfunction "1_1") (pintype "passive"))
      (node (ref "U1") (pin "K7") (pinfunction "IO,_DIFFIO_L11n_K7") (pintype "bidirectional"))
    )
    (net (code "37") (name "Net-(U1A-IO,_DIFFIO_L11p)") (class "Default")
      (node (ref "J57") (pin "1") (pinfunction "1_1") (pintype "passive"))
      (node (ref "U1") (pin "J7") (pinfunction "IO,_DIFFIO_L11p_J7") (pintype "bidirectional"))
    )
    (net (code "38") (name "Net-(U1A-IO,_DIFFIO_L12p,_(DQS0L{slash}CQ1L,DPCLK0){slash}(DQS0L{slash}CQ1L,DPCLK0){slash}(DQS0L{slash}CQ1L,DPCLK0))") (class "Default")
      (node (ref "J59") (pin "1") (pinfunction "1_1") (pintype "passive"))
      (node (ref "U1") (pin "J4") (pinfunction "IO,_DIFFIO_L12p,_(DQS0L/CQ1L,DPCLK0)/(DQS0L/CQ1L,DPCLK0)/(DQS0L/CQ1L,DPCLK0)_J4") (pintype "bidirectional"))
    )
    (net (code "39") (name "Net-(U1A-IO,_DIFFIO_L13n,_(DQ0L){slash}(DQ1L){slash}(DQ1L))") (class "Default")
      (node (ref "J61") (pin "1") (pinfunction "1_1") (pintype "passive"))
      (node (ref "U1") (pin "H1") (pinfunction "IO,_DIFFIO_L13n,_(DQ0L)/(DQ1L)/(DQ1L)_H1") (pintype "bidirectional"))
    )
    (net (code "40") (name "Net-(U1A-IO,_DIFFIO_L13p,_(DQ0L){slash}(DQ1L){slash}(DQ1L))") (class "Default")
      (node (ref "J60") (pin "1") (pinfunction "1_1") (pintype "passive"))
      (node (ref "U1") (pin "H2") (pinfunction "IO,_DIFFIO_L13p,_(DQ0L)/(DQ1L)/(DQ1L)_H2") (pintype "bidirectional"))
    )
    (net (code "41") (name "Net-(U1A-IO,_DIFFIO_L14n)") (class "Default")
      (node (ref "J62") (pin "1") (pinfunction "1_1") (pintype "passive"))
      (node (ref "U1") (pin "J3") (pinfunction "IO,_DIFFIO_L14n_J3") (pintype "bidirectional"))
    )
    (net (code "42") (name "Net-(U1A-IO,_DIFFIO_L15n,_(DQ0L){slash}(DQ1L){slash}(DQ1L))") (class "Default")
      (node (ref "J64") (pin "1") (pinfunction "1_1") (pintype "passive"))
      (node (ref "U1") (pin "J1") (pinfunction "IO,_DIFFIO_L15n,_(DQ0L)/(DQ1L)/(DQ1L)_J1") (pintype "bidirectional"))
    )
    (net (code "43") (name "Net-(U1A-IO,_DIFFIO_L15p,_(DQ0L){slash}(DQ1L){slash}(DQ1L))") (class "Default")
      (node (ref "J63") (pin "1") (pinfunction "1_1") (pintype "passive"))
      (node (ref "U1") (pin "J2") (pinfunction "IO,_DIFFIO_L15p,_(DQ0L)/(DQ1L)/(DQ1L)_J2") (pintype "bidirectional"))
    )
    (net (code "44") (name "Net-(U1A-IO,_VREFB1N0)") (class "Default")
      (node (ref "J49") (pin "1") (pinfunction "1_1") (pintype "passive"))
      (node (ref "U1") (pin "G5") (pinfunction "IO,_VREFB1N0_G5") (pintype "bidirectional"))
    )
    (net (code "45") (name "Net-(U1A-IO,_VREFB1N1)") (class "Default")
      (node (ref "J56") (pin "1") (pinfunction "1_1") (pintype "passive"))
      (node (ref "U1") (pin "H5") (pinfunction "IO,_VREFB1N1_H5") (pintype "bidirectional"))
    )
    (net (code "46") (name "Net-(Y1-OUT)") (class "Default")
      (node (ref "C36") (pin "1") (pinfunction "1_1") (pintype "passive"))
      (node (ref "Y1") (pin "3") (pinfunction "OUT_3") (pintype "passive"))
    )
    (net (code "47") (name "VCC 3.3") (class "Default")
      (node (ref "C1") (pin "2") (pinfunction "2_2") (pintype "passive"))
      (node (ref "C2") (pin "2") (pinfunction "2_2") (pintype "passive"))
      (node (ref "C3") (pin "2") (pinfunction "2_2") (pintype "passive"))
      (node (ref "C34") (pin "2") (pinfunction "2_2") (pintype "passive"))
      (node (ref "C4") (pin "2") (pinfunction "2_2") (pintype "passive"))
      (node (ref "J1") (pin "1") (pinfunction "1_1") (pintype "passive"))
      (node (ref "J2") (pin "1") (pinfunction "1_1") (pintype "passive"))
      (node (ref "J3") (pin "1") (pinfunction "1_1") (pintype "passive"))
      (node (ref "J33") (pin "1") (pinfunction "1_1") (pintype "passive"))
      (node (ref "J34") (pin "1") (pinfunction "1_1") (pintype "passive"))
      (node (ref "J4") (pin "1") (pinfunction "1_1") (pintype "passive"))
      (node (ref "J51") (pin "4") (pinfunction "4_4") (pintype "passive"))
      (node (ref "J66") (pin "5") (pinfunction "5_5") (pintype "passive"))
      (node (ref "R1") (pin "2") (pinfunction "2_2") (pintype "passive"))
      (node (ref "R10") (pin "2") (pinfunction "2_2") (pintype "passive"))
      (node (ref "R11") (pin "2") (pinfunction "2_2") (pintype "passive"))
      (node (ref "R3") (pin "2") (pinfunction "2_2") (pintype "passive"))
      (node (ref "R4") (pin "2") (pinfunction "2_2") (pintype "passive"))
      (node (ref "R5") (pin "2") (pinfunction "2_2") (pintype "passive"))
      (node (ref "R6") (pin "2") (pinfunction "2_2") (pintype "passive"))
      (node (ref "R7") (pin "2") (pinfunction "2_2") (pintype "passive"))
      (node (ref "R8") (pin "2") (pinfunction "2_2") (pintype "passive"))
      (node (ref "R9") (pin "2") (pinfunction "2_2") (pintype "passive"))
      (node (ref "U1") (pin "D4") (pinfunction "VCCIO1_D4") (pintype "power_in"))
      (node (ref "U1") (pin "F4") (pinfunction "VCCIO1_F4") (pintype "power_in"))
      (node (ref "U1") (pin "K4") (pinfunction "VCCIO1_K4") (pintype "power_in"))
      (node (ref "Y1") (pin "4") (pinfunction "VCC_4") (pintype "passive"))
    )
    (net (code "48") (name "VCCA") (class "Default")
      (node (ref "C29") (pin "2") (pinfunction "2_2") (pintype "passive"))
      (node (ref "C30") (pin "2") (pinfunction "2_2") (pintype "passive"))
      (node (ref "C31") (pin "2") (pinfunction "2_2") (pintype "passive"))
      (node (ref "C32") (pin "2") (pinfunction "2_2") (pintype "passive"))
      (node (ref "C33") (pin "2") (pinfunction "2_2") (pintype "passive"))
      (node (ref "J19") (pin "1") (pinfunction "1_1") (pintype "passive"))
      (node (ref "J20") (pin "1") (pinfunction "1_1") (pintype "passive"))
      (node (ref "U1") (pin "F18") (pinfunction "VCCA2_F18") (pintype "power_in"))
      (node (ref "U1") (pin "G6") (pinfunction "VCCA3_G6") (pintype "power_in"))
      (node (ref "U1") (pin "T6") (pinfunction "VCCA1_T6") (pintype "power_in"))
      (node (ref "U1") (pin "U18") (pinfunction "VCCA4_U18") (pintype "power_in"))
    )
    (net (code "49") (name "VCCD") (class "Default")
      (node (ref "C24") (pin "2") (pinfunction "2_2") (pintype "passive"))
      (node (ref "C25") (pin "2") (pinfunction "2_2") (pintype "passive"))
      (node (ref "C26") (pin "2") (pinfunction "2_2") (pintype "passive"))
      (node (ref "C27") (pin "2") (pinfunction "2_2") (pintype "passive"))
      (node (ref "C28") (pin "2") (pinfunction "2_2") (pintype "passive"))
      (node (ref "J17") (pin "1") (pinfunction "1_1") (pintype "passive"))
      (node (ref "J18") (pin "1") (pinfunction "1_1") (pintype "passive"))
      (node (ref "U1") (pin "E17") (pinfunction "VCCD_PLL2_E17") (pintype "power_in"))
      (node (ref "U1") (pin "F6") (pinfunction "VCCD_PLL3_F6") (pintype "power_in"))
      (node (ref "U1") (pin "U6") (pinfunction "VCCD_PLL1_U6") (pintype "power_in"))
      (node (ref "U1") (pin "V17") (pinfunction "VCCD_PLL4_V17") (pintype "power_in"))
    )
    (net (code "50") (name "VCCINT") (class "Default")
      (node (ref "C10") (pin "2") (pinfunction "2_2") (pintype "passive"))
      (node (ref "C11") (pin "2") (pinfunction "2_2") (pintype "passive"))
      (node (ref "C12") (pin "2") (pinfunction "2_2") (pintype "passive"))
      (node (ref "C13") (pin "2") (pinfunction "2_2") (pintype "passive"))
      (node (ref "C14") (pin "2") (pinfunction "2_2") (pintype "passive"))
      (node (ref "C15") (pin "2") (pinfunction "2_2") (pintype "passive"))
      (node (ref "C16") (pin "2") (pinfunction "2_2") (pintype "passive"))
      (node (ref "C17") (pin "2") (pinfunction "2_2") (pintype "passive"))
      (node (ref "C18") (pin "2") (pinfunction "2_2") (pintype "passive"))
      (node (ref "C19") (pin "2") (pinfunction "2_2") (pintype "passive"))
      (node (ref "C20") (pin "2") (pinfunction "2_2") (pintype "passive"))
      (node (ref "C21") (pin "2") (pinfunction "2_2") (pintype "passive"))
      (node (ref "C22") (pin "2") (pinfunction "2_2") (pintype "passive"))
      (node (ref "C23") (pin "2") (pinfunction "2_2") (pintype "passive"))
      (node (ref "C5") (pin "2") (pinfunction "2_2") (pintype "passive"))
      (node (ref "C6") (pin "2") (pinfunction "2_2") (pintype "passive"))
      (node (ref "C7") (pin "2") (pinfunction "2_2") (pintype "passive"))
      (node (ref "C8") (pin "2") (pinfunction "2_2") (pintype "passive"))
      (node (ref "C9") (pin "2") (pinfunction "2_2") (pintype "passive"))
      (node (ref "J5") (pin "1") (pinfunction "1_1") (pintype "passive"))
      (node (ref "J6") (pin "1") (pinfunction "1_1") (pintype "passive"))
      (node (ref "J7") (pin "1") (pinfunction "1_1") (pintype "passive"))
      (node (ref "J8") (pin "1") (pinfunction "1_1") (pintype "passive"))
      (node (ref "U1") (pin "G12") (pinfunction "VCCINT_G12") (pintype "power_in"))
      (node (ref "U1") (pin "H11") (pinfunction "VCCINT_H11") (pintype "power_in"))
      (node (ref "U1") (pin "H15") (pinfunction "VCCINT_H15") (pintype "power_in"))
      (node (ref "U1") (pin "H9") (pinfunction "VCCINT_H9") (pintype "power_in"))
      (node (ref "U1") (pin "J10") (pinfunction "VCCINT_J10") (pintype "power_in"))
      (node (ref "U1") (pin "J11") (pinfunction "VCCINT_J11") (pintype "power_in"))
      (node (ref "U1") (pin "J12") (pinfunction "VCCINT_J12") (pintype "power_in"))
      (node (ref "U1") (pin "J13") (pinfunction "VCCINT_J13") (pintype "power_in"))
      (node (ref "U1") (pin "J14") (pinfunction "VCCINT_J14") (pintype "power_in"))
      (node (ref "U1") (pin "J16") (pinfunction "VCCINT_J16") (pintype "power_in"))
      (node (ref "U1") (pin "J8") (pinfunction "VCCINT_J8") (pintype "power_in"))
      (node (ref "U1") (pin "K14") (pinfunction "VCCINT_K14") (pintype "power_in"))
      (node (ref "U1") (pin "K15") (pinfunction "VCCINT_K15") (pintype "power_in"))
      (node (ref "U1") (pin "K8") (pinfunction "VCCINT_K8") (pintype "power_in"))
      (node (ref "U1") (pin "K9") (pinfunction "VCCINT_K9") (pintype "power_in"))
      (node (ref "U1") (pin "L14") (pinfunction "VCCINT_L14") (pintype "power_in"))
      (node (ref "U1") (pin "L16") (pinfunction "VCCINT_L16") (pintype "power_in"))
      (node (ref "U1") (pin "L7") (pinfunction "VCCINT_L7") (pintype "power_in"))
      (node (ref "U1") (pin "L9") (pinfunction "VCCINT_L9") (pintype "power_in"))
      (node (ref "U1") (pin "M14") (pinfunction "VCCINT_M14") (pintype "power_in"))
      (node (ref "U1") (pin "M15") (pinfunction "VCCINT_M15") (pintype "power_in"))
      (node (ref "U1") (pin "M8") (pinfunction "VCCINT_M8") (pintype "power_in"))
      (node (ref "U1") (pin "M9") (pinfunction "VCCINT_M9") (pintype "power_in"))
      (node (ref "U1") (pin "N14") (pinfunction "VCCINT_N14") (pintype "power_in"))
      (node (ref "U1") (pin "N9") (pinfunction "VCCINT_N9") (pintype "power_in"))
      (node (ref "U1") (pin "P10") (pinfunction "VCCINT_P10") (pintype "power_in"))
      (node (ref "U1") (pin "P11") (pinfunction "VCCINT_P11") (pintype "power_in"))
      (node (ref "U1") (pin "P12") (pinfunction "VCCINT_P12") (pintype "power_in"))
      (node (ref "U1") (pin "P13") (pinfunction "VCCINT_P13") (pintype "power_in"))
      (node (ref "U1") (pin "P14") (pinfunction "VCCINT_P14") (pintype "power_in"))
      (node (ref "U1") (pin "P15") (pinfunction "VCCINT_P15") (pintype "power_in"))
      (node (ref "U1") (pin "P9") (pinfunction "VCCINT_P9") (pintype "power_in"))
      (node (ref "U1") (pin "R10") (pinfunction "VCCINT_R10") (pintype "power_in"))
      (node (ref "U1") (pin "R12") (pinfunction "VCCINT_R12") (pintype "power_in"))
      (node (ref "U1") (pin "R8") (pinfunction "VCCINT_R8") (pintype "power_in"))
      (node (ref "U1") (pin "T13") (pinfunction "VCCINT_T13") (pintype "power_in"))
      (node (ref "U1") (pin "T7") (pinfunction "VCCINT_T7") (pintype "power_in"))
      (node (ref "U1") (pin "T9") (pinfunction "VCCINT_T9") (pintype "power_in"))
    )
    (net (code "51") (name "unconnected-(J51-Pad6)") (class "Default")
      (node (ref "J51") (pin "6") (pinfunction "6_6") (pintype "passive+no_connect"))
    )
    (net (code "52") (name "unconnected-(J51-Pad7)") (class "Default")
      (node (ref "J51") (pin "7") (pinfunction "7_7") (pintype "passive+no_connect"))
    )
    (net (code "53") (name "unconnected-(J51-Pad8)") (class "Default")
      (node (ref "J51") (pin "8") (pinfunction "8_8") (pintype "passive+no_connect"))
    )
    (net (code "54") (name "unconnected-(U1B-IO,_(DQS3L{slash}CQ3L#,CDPCLK1){slash}(DQS3L{slash}CQ3L#,CDPCLK1){slash}(DQS3L{slash}CQ3L#,CDPCLK1)-PadT4)") (class "Default")
      (node (ref "U1") (pin "T4") (pinfunction "IO,_(DQS3L/CQ3L#,CDPCLK1)/(DQS3L/CQ3L#,CDPCLK1)/(DQS3L/CQ3L#,CDPCLK1)_T4") (pintype "bidirectional+no_connect"))
    )
    (net (code "55") (name "unconnected-(U1B-IO,_DIFFIO_L16n,_(DQ0L){slash}(DQ1L){slash}(DQ1L)-PadM6)") (class "Default")
      (node (ref "U1") (pin "M6") (pinfunction "IO,_DIFFIO_L16n,_(DQ0L)/(DQ1L)/(DQ1L)_M6") (pintype "bidirectional+no_connect"))
    )
    (net (code "56") (name "unconnected-(U1B-IO,_DIFFIO_L16p,_(DQ0L){slash}(DQ1L){slash}(DQ1L)-PadL6)") (class "Default")
      (node (ref "U1") (pin "L6") (pinfunction "IO,_DIFFIO_L16p,_(DQ0L)/(DQ1L)/(DQ1L)_L6") (pintype "bidirectional+no_connect"))
    )
    (net (code "57") (name "unconnected-(U1B-IO,_DIFFIO_L17n,__{slash}(DQ1L){slash}(DQ1L)-PadM1)") (class "Default")
      (node (ref "U1") (pin "M1") (pinfunction "IO,_DIFFIO_L17n,__/(DQ1L)/(DQ1L)_M1") (pintype "bidirectional+no_connect"))
    )
    (net (code "58") (name "unconnected-(U1B-IO,_DIFFIO_L17p,_(DQ0L){slash}(DQ1L){slash}(DQ1L)-PadM2)") (class "Default")
      (node (ref "U1") (pin "M2") (pinfunction "IO,_DIFFIO_L17p,_(DQ0L)/(DQ1L)/(DQ1L)_M2") (pintype "bidirectional+no_connect"))
    )
    (net (code "59") (name "unconnected-(U1B-IO,_DIFFIO_L18n,_(DQ1L){slash}(DQ3L){slash}(DQ1L)-PadM3)") (class "Default")
      (node (ref "U1") (pin "M3") (pinfunction "IO,_DIFFIO_L18n,_(DQ1L)/(DQ3L)/(DQ1L)_M3") (pintype "bidirectional+no_connect"))
    )
    (net (code "60") (name "unconnected-(U1B-IO,_DIFFIO_L18p,_(DM0L){slash}(DM1L{slash}BWS#1L){slash}(DM1L{slash}BWS#1L)-PadM4)") (class "Default")
      (node (ref "U1") (pin "M4") (pinfunction "IO,_DIFFIO_L18p,_(DM0L)/(DM1L/BWS#1L)/(DM1L/BWS#1L)_M4") (pintype "bidirectional+no_connect"))
    )
    (net (code "61") (name "unconnected-(U1B-IO,_DIFFIO_L19n,_(DQ1L){slash}(DQ3L){slash}(DQ1L)-PadN1)") (class "Default")
      (node (ref "U1") (pin "N1") (pinfunction "IO,_DIFFIO_L19n,_(DQ1L)/(DQ3L)/(DQ1L)_N1") (pintype "bidirectional+no_connect"))
    )
    (net (code "62") (name "unconnected-(U1B-IO,_DIFFIO_L19p,_(DQ1L){slash}(DQ3L){slash}(DQ1L)-PadN2)") (class "Default")
      (node (ref "U1") (pin "N2") (pinfunction "IO,_DIFFIO_L19p,_(DQ1L)/(DQ3L)/(DQ1L)_N2") (pintype "bidirectional+no_connect"))
    )
    (net (code "63") (name "unconnected-(U1B-IO,_DIFFIO_L20n,_(DQ1L){slash}(DQ3L){slash}(DQ1L)-PadP1)") (class "Default")
      (node (ref "U1") (pin "P1") (pinfunction "IO,_DIFFIO_L20n,_(DQ1L)/(DQ3L)/(DQ1L)_P1") (pintype "bidirectional+no_connect"))
    )
    (net (code "64") (name "unconnected-(U1B-IO,_DIFFIO_L20p,_(DQ1L){slash}(DQ3L){slash}(DQ1L)-PadP2)") (class "Default")
      (node (ref "U1") (pin "P2") (pinfunction "IO,_DIFFIO_L20p,_(DQ1L)/(DQ3L)/(DQ1L)_P2") (pintype "bidirectional+no_connect"))
    )
    (net (code "65") (name "unconnected-(U1B-IO,_DIFFIO_L21n,_(DQ1L){slash}(DQ3L){slash}(DQ1L)-PadR1)") (class "Default")
      (node (ref "U1") (pin "R1") (pinfunction "IO,_DIFFIO_L21n,_(DQ1L)/(DQ3L)/(DQ1L)_R1") (pintype "bidirectional+no_connect"))
    )
    (net (code "66") (name "unconnected-(U1B-IO,_DIFFIO_L21p,_(DQ1L){slash}(DQ3L){slash}(DQ1L)-PadR2)") (class "Default")
      (node (ref "U1") (pin "R2") (pinfunction "IO,_DIFFIO_L21p,_(DQ1L)/(DQ3L)/(DQ1L)_R2") (pintype "bidirectional+no_connect"))
    )
    (net (code "67") (name "unconnected-(U1B-IO,_DIFFIO_L22n,_(DQ1L){slash}(DQ3L){slash}(DQ1L)-PadN5)") (class "Default")
      (node (ref "U1") (pin "N5") (pinfunction "IO,_DIFFIO_L22n,_(DQ1L)/(DQ3L)/(DQ1L)_N5") (pintype "bidirectional+no_connect"))
    )
    (net (code "68") (name "unconnected-(U1B-IO,_DIFFIO_L23n,_(DQ1L){slash}(DQ3L){slash}(DQ1L)-PadP3)") (class "Default")
      (node (ref "U1") (pin "P3") (pinfunction "IO,_DIFFIO_L23n,_(DQ1L)/(DQ3L)/(DQ1L)_P3") (pintype "bidirectional+no_connect"))
    )
    (net (code "69") (name "unconnected-(U1B-IO,_DIFFIO_L23p,_(DQS1L{slash}CQ1L#,DPCLK1){slash}(DQS1L{slash}CQ1L#,DPCLK1){slash}(DQS1L{slash}CQ1L#,DPCLK1)-PadP4)") (class "Default")
      (node (ref "U1") (pin "P4") (pinfunction "IO,_DIFFIO_L23p,_(DQS1L/CQ1L#,DPCLK1)/(DQS1L/CQ1L#,DPCLK1)/(DQS1L/CQ1L#,DPCLK1)_P4") (pintype "bidirectional+no_connect"))
    )
    (net (code "70") (name "unconnected-(U1B-IO,_DIFFIO_L24n,_(DQ3L){slash}(DQ3L){slash}(DQ1L)-PadU1)") (class "Default")
      (node (ref "U1") (pin "U1") (pinfunction "IO,_DIFFIO_L24n,_(DQ3L)/(DQ3L)/(DQ1L)_U1") (pintype "bidirectional+no_connect"))
    )
    (net (code "71") (name "unconnected-(U1B-IO,_DIFFIO_L24p,_(DM1L{slash}BWS#1L){slash}(DM3L{slash}BWS#3L){slash}(DM1L{slash}BWS#1L)-PadU2)") (class "Default")
      (node (ref "U1") (pin "U2") (pinfunction "IO,_DIFFIO_L24p,_(DM1L/BWS#1L)/(DM3L/BWS#3L)/(DM1L/BWS#1L)_U2") (pintype "bidirectional+no_connect"))
    )
    (net (code "72") (name "unconnected-(U1B-IO,_DIFFIO_L25n,_(DQ3L){slash}(DQ3L){slash}(DQ1L)-PadV1)") (class "Default")
      (node (ref "U1") (pin "V1") (pinfunction "IO,_DIFFIO_L25n,_(DQ3L)/(DQ3L)/(DQ1L)_V1") (pintype "bidirectional+no_connect"))
    )
    (net (code "73") (name "unconnected-(U1B-IO,_DIFFIO_L25p,_(DQ3L){slash}(DQ3L){slash}(DQ1L)-PadV2)") (class "Default")
      (node (ref "U1") (pin "V2") (pinfunction "IO,_DIFFIO_L25p,_(DQ3L)/(DQ3L)/(DQ1L)_V2") (pintype "bidirectional+no_connect"))
    )
    (net (code "74") (name "unconnected-(U1B-IO,_DIFFIO_L26n,_(DQ3L){slash}(DQ3L){slash}(DQ1L)-PadN6)") (class "Default")
      (node (ref "U1") (pin "N6") (pinfunction "IO,_DIFFIO_L26n,_(DQ3L)/(DQ3L)/(DQ1L)_N6") (pintype "bidirectional+no_connect"))
    )
    (net (code "75") (name "unconnected-(U1B-IO,_DIFFIO_L26p-PadP5)") (class "Default")
      (node (ref "U1") (pin "P5") (pinfunction "IO,_DIFFIO_L26p_P5") (pintype "bidirectional+no_connect"))
    )
    (net (code "76") (name "unconnected-(U1B-IO,_DIFFIO_L27n-PadR3)") (class "Default")
      (node (ref "U1") (pin "R3") (pinfunction "IO,_DIFFIO_L27n_R3") (pintype "bidirectional+no_connect"))
    )
    (net (code "77") (name "unconnected-(U1B-IO,_DIFFIO_L27p-PadR4)") (class "Default")
      (node (ref "U1") (pin "R4") (pinfunction "IO,_DIFFIO_L27p_R4") (pintype "bidirectional+no_connect"))
    )
    (net (code "78") (name "unconnected-(U1B-IO,_DIFFIO_L28n,_(DQ3L){slash}(DQ3L){slash}(DQ1L)-PadW1)") (class "Default")
      (node (ref "U1") (pin "W1") (pinfunction "IO,_DIFFIO_L28n,_(DQ3L)/(DQ3L)/(DQ1L)_W1") (pintype "bidirectional+no_connect"))
    )
    (net (code "79") (name "unconnected-(U1B-IO,_DIFFIO_L28p,_(DQ3L){slash}(DQ3L){slash}(DQ1L)-PadW2)") (class "Default")
      (node (ref "U1") (pin "W2") (pinfunction "IO,_DIFFIO_L28p,_(DQ3L)/(DQ3L)/(DQ1L)_W2") (pintype "bidirectional+no_connect"))
    )
    (net (code "80") (name "unconnected-(U1B-IO,_DIFFIO_L29n,_(DQ3L){slash}(DQ3L){slash}(DQ1L)-PadY1)") (class "Default")
      (node (ref "U1") (pin "Y1") (pinfunction "IO,_DIFFIO_L29n,_(DQ3L)/(DQ3L)/(DQ1L)_Y1") (pintype "bidirectional+no_connect"))
    )
    (net (code "81") (name "unconnected-(U1B-IO,_DIFFIO_L29p,_(DQ3L){slash}(DQ3L){slash}(DQ1L)-PadY2)") (class "Default")
      (node (ref "U1") (pin "Y2") (pinfunction "IO,_DIFFIO_L29p,_(DQ3L)/(DQ3L)/(DQ1L)_Y2") (pintype "bidirectional+no_connect"))
    )
    (net (code "82") (name "unconnected-(U1B-IO,_DIFFIO_L30n-PadP7)") (class "Default")
      (node (ref "U1") (pin "P7") (pinfunction "IO,_DIFFIO_L30n_P7") (pintype "bidirectional+no_connect"))
    )
    (net (code "83") (name "unconnected-(U1B-IO,_DIFFIO_L30p-PadN7)") (class "Default")
      (node (ref "U1") (pin "N7") (pinfunction "IO,_DIFFIO_L30p_N7") (pintype "bidirectional+no_connect"))
    )
    (net (code "84") (name "unconnected-(U1B-IO,_DIFFIO_L31n,_(DQ3L){slash}(DQ3L){slash}(DQ1L)-PadAA1)") (class "Default")
      (node (ref "U1") (pin "AA1") (pinfunction "IO,_DIFFIO_L31n,_(DQ3L)/(DQ3L)/(DQ1L)_AA1") (pintype "bidirectional+no_connect"))
    )
    (net (code "85") (name "unconnected-(U1B-IO,_DIFFIO_L32n-PadR5)") (class "Default")
      (node (ref "U1") (pin "R5") (pinfunction "IO,_DIFFIO_L32n_R5") (pintype "bidirectional+no_connect"))
    )
    (net (code "86") (name "unconnected-(U1B-IO,_DIFFIO_L32p-PadP6)") (class "Default")
      (node (ref "U1") (pin "P6") (pinfunction "IO,_DIFFIO_L32p_P6") (pintype "bidirectional+no_connect"))
    )
    (net (code "87") (name "unconnected-(U1B-IO,_DIFFIO_L33n-PadR6)") (class "Default")
      (node (ref "U1") (pin "R6") (pinfunction "IO,_DIFFIO_L33n_R6") (pintype "bidirectional+no_connect"))
    )
    (net (code "88") (name "unconnected-(U1B-IO,_DIFFIO_L33p,_(DM3L{slash}BWS#3L){slash}(DM3L{slash}BWS#3L){slash}(DM1L{slash}BWS#1L)-PadT5)") (class "Default")
      (node (ref "U1") (pin "T5") (pinfunction "IO,_DIFFIO_L33p,_(DM3L/BWS#3L)/(DM3L/BWS#3L)/(DM1L/BWS#1L)_T5") (pintype "bidirectional+no_connect"))
    )
    (net (code "89") (name "unconnected-(U1B-IO,_RDN1-PadV3)") (class "Default")
      (node (ref "U1") (pin "V3") (pinfunction "IO,_RDN1_V3") (pintype "bidirectional+no_connect"))
    )
    (net (code "90") (name "unconnected-(U1B-IO,_RUP1-PadV4)") (class "Default")
      (node (ref "U1") (pin "V4") (pinfunction "IO,_RUP1_V4") (pintype "bidirectional+no_connect"))
    )
    (net (code "91") (name "unconnected-(U1B-IO,_VREFB2N0-PadM5)") (class "Default")
      (node (ref "U1") (pin "M5") (pinfunction "IO,_VREFB2N0_M5") (pintype "bidirectional+no_connect"))
    )
    (net (code "92") (name "unconnected-(U1B-IO,_VREFB2N1-PadT3)") (class "Default")
      (node (ref "U1") (pin "T3") (pinfunction "IO,_VREFB2N1_T3") (pintype "bidirectional+no_connect"))
    )
    (net (code "93") (name "unconnected-(U1C-IO,_(DQ3B){slash}(DQ3B){slash}(DQ5B)-PadAA4)") (class "Default")
      (node (ref "U1") (pin "AA4") (pinfunction "IO,_(DQ3B)/(DQ3B)/(DQ5B)_AA4") (pintype "bidirectional+no_connect"))
    )
    (net (code "94") (name "unconnected-(U1C-IO,_(DQ3B){slash}(DQ3B){slash}(DQ5B)-PadW8)") (class "Default")
      (node (ref "U1") (pin "W8") (pinfunction "IO,_(DQ3B)/(DQ3B)/(DQ5B)_W8") (pintype "bidirectional+no_connect"))
    )
    (net (code "95") (name "unconnected-(U1C-IO,_(DQS1B{slash}CQ1B#,CDPCLK2){slash}(DQS1B{slash}CQ1B#,CDPCLK2){slash}(DQS1B{slash}CQ1B#,CDPCLK2)-PadY6)") (class "Default")
      (node (ref "U1") (pin "Y6") (pinfunction "IO,_(DQS1B/CQ1B#,CDPCLK2)/(DQS1B/CQ1B#,CDPCLK2)/(DQS1B/CQ1B#,CDPCLK2)_Y6") (pintype "bidirectional+no_connect"))
    )
    (net (code "96") (name "unconnected-(U1C-IO,_DIFFIO_B1n,_(DM3B{slash}BWS#3B){slash}(DM3B{slash}BWS#3B){slash}(DM5B{slash}BWS#5B)-PadV5)") (class "Default")
      (node (ref "U1") (pin "V5") (pinfunction "IO,_DIFFIO_B1n,_(DM3B/BWS#3B)/(DM3B/BWS#3B)/(DM5B/BWS#5B)_V5") (pintype "bidirectional+no_connect"))
    )
    (net (code "97") (name "unconnected-(U1C-IO,_DIFFIO_B1p-PadV6)") (class "Default")
      (node (ref "U1") (pin "V6") (pinfunction "IO,_DIFFIO_B1p_V6") (pintype "bidirectional+no_connect"))
    )
    (net (code "98") (name "unconnected-(U1C-IO,_DIFFIO_B2n-PadU8)") (class "Default")
      (node (ref "U1") (pin "U8") (pinfunction "IO,_DIFFIO_B2n_U8") (pintype "bidirectional+no_connect"))
    )
    (net (code "99") (name "unconnected-(U1C-IO,_DIFFIO_B2p-PadU7)") (class "Default")
      (node (ref "U1") (pin "U7") (pinfunction "IO,_DIFFIO_B2p_U7") (pintype "bidirectional+no_connect"))
    )
    (net (code "100") (name "unconnected-(U1C-IO,_DIFFIO_B3n,_(DQ3B){slash}(DQ3B){slash}(DQ5B)-PadY3)") (class "Default")
      (node (ref "U1") (pin "Y3") (pinfunction "IO,_DIFFIO_B3n,_(DQ3B)/(DQ3B)/(DQ5B)_Y3") (pintype "bidirectional+no_connect"))
    )
    (net (code "101") (name "unconnected-(U1C-IO,_DIFFIO_B3p-PadY4)") (class "Default")
      (node (ref "U1") (pin "Y4") (pinfunction "IO,_DIFFIO_B3p_Y4") (pintype "bidirectional+no_connect"))
    )
    (net (code "102") (name "unconnected-(U1C-IO,_DIFFIO_B4n-PadV7)") (class "Default")
      (node (ref "U1") (pin "V7") (pinfunction "IO,_DIFFIO_B4n_V7") (pintype "bidirectional+no_connect"))
    )
    (net (code "103") (name "unconnected-(U1C-IO,_DIFFIO_B4p,_(DQ3B){slash}(DQ3B){slash}(DQ5B)-PadW6)") (class "Default")
      (node (ref "U1") (pin "W6") (pinfunction "IO,_DIFFIO_B4p,_(DQ3B)/(DQ3B)/(DQ5B)_W6") (pintype "bidirectional+no_connect"))
    )
    (net (code "104") (name "unconnected-(U1C-IO,_DIFFIO_B5n-PadAA6)") (class "Default")
      (node (ref "U1") (pin "AA6") (pinfunction "IO,_DIFFIO_B5n_AA6") (pintype "bidirectional+no_connect"))
    )
    (net (code "105") (name "unconnected-(U1C-IO,_DIFFIO_B5p,_(DQ3B){slash}(DQ3B){slash}(DQ5B)-PadAA5)") (class "Default")
      (node (ref "U1") (pin "AA5") (pinfunction "IO,_DIFFIO_B5p,_(DQ3B)/(DQ3B)/(DQ5B)_AA5") (pintype "bidirectional+no_connect"))
    )
    (net (code "106") (name "unconnected-(U1C-IO,_DIFFIO_B6n-PadAB5)") (class "Default")
      (node (ref "U1") (pin "AB5") (pinfunction "IO,_DIFFIO_B6n_AB5") (pintype "bidirectional+no_connect"))
    )
    (net (code "107") (name "unconnected-(U1C-IO,_DIFFIO_B6p-PadAB6)") (class "Default")
      (node (ref "U1") (pin "AB6") (pinfunction "IO,_DIFFIO_B6p_AB6") (pintype "bidirectional+no_connect"))
    )
    (net (code "108") (name "unconnected-(U1C-IO,_DIFFIO_B7n,_(DQ3B){slash}(DQ3B){slash}(DQ5B)-PadY7)") (class "Default")
      (node (ref "U1") (pin "Y7") (pinfunction "IO,_DIFFIO_B7n,_(DQ3B)/(DQ3B)/(DQ5B)_Y7") (pintype "bidirectional+no_connect"))
    )
    (net (code "109") (name "unconnected-(U1C-IO,_DIFFIO_B7p,_(DQ3B){slash}(DQ3B){slash}(DQ5B)-PadW7)") (class "Default")
      (node (ref "U1") (pin "W7") (pinfunction "IO,_DIFFIO_B7p,_(DQ3B)/(DQ3B)/(DQ5B)_W7") (pintype "bidirectional+no_connect"))
    )
    (net (code "110") (name "unconnected-(U1C-IO,_DIFFIO_B8n,_(DQ3B){slash}(DQ3B){slash}(DQ5B)-PadV8)") (class "Default")
      (node (ref "U1") (pin "V8") (pinfunction "IO,_DIFFIO_B8n,_(DQ3B)/(DQ3B)/(DQ5B)_V8") (pintype "bidirectional+no_connect"))
    )
    (net (code "111") (name "unconnected-(U1C-IO,_DIFFIO_B8p,_(DQ3B){slash}(DQ3B){slash}(DQ5B)-PadU9)") (class "Default")
      (node (ref "U1") (pin "U9") (pinfunction "IO,_DIFFIO_B8p,_(DQ3B)/(DQ3B)/(DQ5B)_U9") (pintype "bidirectional+no_connect"))
    )
    (net (code "112") (name "unconnected-(U1C-IO,_DIFFIO_B10n,_(DQ5B){slash}(DQ3B){slash}(DQ5B)-PadAB7)") (class "Default")
      (node (ref "U1") (pin "AB7") (pinfunction "IO,_DIFFIO_B10n,_(DQ5B)/(DQ3B)/(DQ5B)_AB7") (pintype "bidirectional+no_connect"))
    )
    (net (code "113") (name "unconnected-(U1C-IO,_DIFFIO_B10p,_(DM5B{slash}BWS#5B){slash}(DM3B{slash}BWS#3B){slash}(DM5B{slash}BWS#5B)-PadAA7)") (class "Default")
      (node (ref "U1") (pin "AA7") (pinfunction "IO,_DIFFIO_B10p,_(DM5B/BWS#5B)/(DM3B/BWS#3B)/(DM5B/BWS#5B)_AA7") (pintype "bidirectional+no_connect"))
    )
    (net (code "114") (name "unconnected-(U1C-IO,_DIFFIO_B11p,_(DQ5B){slash}(DQ3B){slash}(DQ5B)-PadY8)") (class "Default")
      (node (ref "U1") (pin "Y8") (pinfunction "IO,_DIFFIO_B11p,_(DQ5B)/(DQ3B)/(DQ5B)_Y8") (pintype "bidirectional+no_connect"))
    )
    (net (code "115") (name "unconnected-(U1C-IO,_DIFFIO_B13n-PadT11)") (class "Default")
      (node (ref "U1") (pin "T11") (pinfunction "IO,_DIFFIO_B13n_T11") (pintype "bidirectional+no_connect"))
    )
    (net (code "116") (name "unconnected-(U1C-IO,_DIFFIO_B13p-PadT10)") (class "Default")
      (node (ref "U1") (pin "T10") (pinfunction "IO,_DIFFIO_B13p_T10") (pintype "bidirectional+no_connect"))
    )
    (net (code "117") (name "unconnected-(U1C-IO,_DIFFIO_B15p,_(DQS3B{slash}CQ3B#,DPCLK2){slash}(DQS3B{slash}CQ3B#,DPCLK2){slash}(DQS3B{slash}CQ3B#,DPCLK2)-PadV10)") (class "Default")
      (node (ref "U1") (pin "V10") (pinfunction "IO,_DIFFIO_B15p,_(DQS3B/CQ3B#,DPCLK2)/(DQS3B/CQ3B#,DPCLK2)/(DQS3B/CQ3B#,DPCLK2)_V10") (pintype "bidirectional+no_connect"))
    )
    (net (code "118") (name "unconnected-(U1C-IO,_DIFFIO_B16n,_(DQ5B){slash}(DQ3B){slash}(DQ5B)-PadU10)") (class "Default")
      (node (ref "U1") (pin "U10") (pinfunction "IO,_DIFFIO_B16n,_(DQ5B)/(DQ3B)/(DQ5B)_U10") (pintype "bidirectional+no_connect"))
    )
    (net (code "119") (name "unconnected-(U1C-IO,_DIFFIO_B17n,_(DQ5B){slash}(DQ3B){slash}(DQ5B)-PadAB8)") (class "Default")
      (node (ref "U1") (pin "AB8") (pinfunction "IO,_DIFFIO_B17n,_(DQ5B)/(DQ3B)/(DQ5B)_AB8") (pintype "bidirectional+no_connect"))
    )
    (net (code "120") (name "unconnected-(U1C-IO,_DIFFIO_B17p,_(DQ5B){slash}(DQ3B){slash}(DQ5B)-PadAA8)") (class "Default")
      (node (ref "U1") (pin "AA8") (pinfunction "IO,_DIFFIO_B17p,_(DQ5B)/(DQ3B)/(DQ5B)_AA8") (pintype "bidirectional+no_connect"))
    )
    (net (code "121") (name "unconnected-(U1C-IO,_DIFFIO_B18n,_(DQS5B{slash}CQ5B#,DPCLK3){slash}(DQS5B{slash}CQ5B#,DPCLK3){slash}(DQS5B{slash}CQ5B#,DPCLK3)-PadAB9)") (class "Default")
      (node (ref "U1") (pin "AB9") (pinfunction "IO,_DIFFIO_B18n,_(DQS5B/CQ5B#,DPCLK3)/(DQS5B/CQ5B#,DPCLK3)/(DQS5B/CQ5B#,DPCLK3)_AB9") (pintype "bidirectional+no_connect"))
    )
    (net (code "122") (name "unconnected-(U1C-IO,_DIFFIO_B18p,_(DQ5B){slash}(DQ3B){slash}(DQ5B)-PadAA9)") (class "Default")
      (node (ref "U1") (pin "AA9") (pinfunction "IO,_DIFFIO_B18p,_(DQ5B)/(DQ3B)/(DQ5B)_AA9") (pintype "bidirectional+no_connect"))
    )
    (net (code "123") (name "unconnected-(U1C-IO,_DIFFIO_B19n,_(DQ5B){slash}(DQ3B){slash}(DQ5B)-PadV11)") (class "Default")
      (node (ref "U1") (pin "V11") (pinfunction "IO,_DIFFIO_B19n,_(DQ5B)/(DQ3B)/(DQ5B)_V11") (pintype "bidirectional+no_connect"))
    )
    (net (code "124") (name "unconnected-(U1C-IO,_DIFFIO_B19p-PadU11)") (class "Default")
      (node (ref "U1") (pin "U11") (pinfunction "IO,_DIFFIO_B19p_U11") (pintype "bidirectional+no_connect"))
    )
    (net (code "125") (name "unconnected-(U1C-IO,_DIFFIO_B20n,_(DQ5B){slash}(DQ3B){slash}(DQ5B)-PadY10)") (class "Default")
      (node (ref "U1") (pin "Y10") (pinfunction "IO,_DIFFIO_B20n,_(DQ5B)/(DQ3B)/(DQ5B)_Y10") (pintype "bidirectional+no_connect"))
    )
    (net (code "126") (name "unconnected-(U1C-IO,_DIFFIO_B20p,_(DQ5B){slash}(DQ3B){slash}(DQ5B)-PadW10)") (class "Default")
      (node (ref "U1") (pin "W10") (pinfunction "IO,_DIFFIO_B20p,_(DQ5B)/(DQ3B)/(DQ5B)_W10") (pintype "bidirectional+no_connect"))
    )
    (net (code "127") (name "unconnected-(U1C-IO,_DIFFIO_B21n,__{slash}(DQ5B){slash}(DQ5B)-PadAB10)") (class "Default")
      (node (ref "U1") (pin "AB10") (pinfunction "IO,_DIFFIO_B21n,__/(DQ5B)/(DQ5B)_AB10") (pintype "bidirectional+no_connect"))
    )
    (net (code "128") (name "unconnected-(U1C-IO,_DIFFIO_B21p,_(DM4B){slash}(DM5B{slash}BWS#5B){slash}(DM5B{slash}BWS#5B)-PadAA10)") (class "Default")
      (node (ref "U1") (pin "AA10") (pinfunction "IO,_DIFFIO_B21p,_(DM4B)/(DM5B/BWS#5B)/(DM5B/BWS#5B)_AA10") (pintype "bidirectional+no_connect"))
    )
    (net (code "129") (name "unconnected-(U1C-IO,_PLL1_CLKOUTn-PadAB3)") (class "Default")
      (node (ref "U1") (pin "AB3") (pinfunction "IO,_PLL1_CLKOUTn_AB3") (pintype "bidirectional+no_connect"))
    )
    (net (code "130") (name "unconnected-(U1C-IO,_PLL1_CLKOUTp-PadAA3)") (class "Default")
      (node (ref "U1") (pin "AA3") (pinfunction "IO,_PLL1_CLKOUTp_AA3") (pintype "bidirectional+no_connect"))
    )
    (net (code "131") (name "unconnected-(U1C-IO,_VREFB3N0-PadV9)") (class "Default")
      (node (ref "U1") (pin "V9") (pinfunction "IO,_VREFB3N0_V9") (pintype "bidirectional+no_connect"))
    )
    (net (code "132") (name "unconnected-(U1C-IO,_VREFB3N1-PadAB4)") (class "Default")
      (node (ref "U1") (pin "AB4") (pinfunction "IO,_VREFB3N1_AB4") (pintype "bidirectional+no_connect"))
    )
    (net (code "133") (name "unconnected-(U1D-IO,_(DQ2B){slash}(DQ5B){slash}(DQ5B)-PadAB18)") (class "Default")
      (node (ref "U1") (pin "AB18") (pinfunction "IO,_(DQ2B)/(DQ5B)/(DQ5B)_AB18") (pintype "bidirectional+no_connect"))
    )
    (net (code "134") (name "unconnected-(U1D-IO,_DIFFIO_B23n,_(DQ4B){slash}(DQ5B){slash}(DQ5B)-PadAB13)") (class "Default")
      (node (ref "U1") (pin "AB13") (pinfunction "IO,_DIFFIO_B23n,_(DQ4B)/(DQ5B)/(DQ5B)_AB13") (pintype "bidirectional+no_connect"))
    )
    (net (code "135") (name "unconnected-(U1D-IO,_DIFFIO_B23p,_(DQ4B){slash}(DQ5B){slash}(DQ5B)-PadAA13)") (class "Default")
      (node (ref "U1") (pin "AA13") (pinfunction "IO,_DIFFIO_B23p,_(DQ4B)/(DQ5B)/(DQ5B)_AA13") (pintype "bidirectional+no_connect"))
    )
    (net (code "136") (name "unconnected-(U1D-IO,_DIFFIO_B25n,_(DQ4B){slash}(DQ5B){slash}(DQ5B)-PadAB14)") (class "Default")
      (node (ref "U1") (pin "AB14") (pinfunction "IO,_DIFFIO_B25n,_(DQ4B)/(DQ5B)/(DQ5B)_AB14") (pintype "bidirectional+no_connect"))
    )
    (net (code "137") (name "unconnected-(U1D-IO,_DIFFIO_B25p,_(DQ4B){slash}(DQ5B){slash}(DQ5B)-PadAA14)") (class "Default")
      (node (ref "U1") (pin "AA14") (pinfunction "IO,_DIFFIO_B25p,_(DQ4B)/(DQ5B)/(DQ5B)_AA14") (pintype "bidirectional+no_connect"))
    )
    (net (code "138") (name "unconnected-(U1D-IO,_DIFFIO_B26n,_(DQS4B{slash}CQ5B,DPCLK4){slash}(DQS4B{slash}CQ5B,DPCLK4){slash}(DQS4B{slash}CQ5B,DPCLK4)-PadY13)") (class "Default")
      (node (ref "U1") (pin "Y13") (pinfunction "IO,_DIFFIO_B26n,_(DQS4B/CQ5B,DPCLK4)/(DQS4B/CQ5B,DPCLK4)/(DQS4B/CQ5B,DPCLK4)_Y13") (pintype "bidirectional+no_connect"))
    )
    (net (code "139") (name "unconnected-(U1D-IO,_DIFFIO_B26p,_(DQ4B){slash}(DQ5B){slash}(DQ5B)-PadW13)") (class "Default")
      (node (ref "U1") (pin "W13") (pinfunction "IO,_DIFFIO_B26p,_(DQ4B)/(DQ5B)/(DQ5B)_W13") (pintype "bidirectional+no_connect"))
    )
    (net (code "140") (name "unconnected-(U1D-IO,_DIFFIO_B27n,_(DQ4B){slash}(DQ5B){slash}(DQ5B)-PadAB15)") (class "Default")
      (node (ref "U1") (pin "AB15") (pinfunction "IO,_DIFFIO_B27n,_(DQ4B)/(DQ5B)/(DQ5B)_AB15") (pintype "bidirectional+no_connect"))
    )
    (net (code "141") (name "unconnected-(U1D-IO,_DIFFIO_B27p,_(DQ4B){slash}(DQ5B){slash}(DQ5B)-PadAA15)") (class "Default")
      (node (ref "U1") (pin "AA15") (pinfunction "IO,_DIFFIO_B27p,_(DQ4B)/(DQ5B)/(DQ5B)_AA15") (pintype "bidirectional+no_connect"))
    )
    (net (code "142") (name "unconnected-(U1D-IO,_DIFFIO_B28p,_(DQ4B){slash}(DQ5B){slash}(DQ5B)-PadU12)") (class "Default")
      (node (ref "U1") (pin "U12") (pinfunction "IO,_DIFFIO_B28p,_(DQ4B)/(DQ5B)/(DQ5B)_U12") (pintype "bidirectional+no_connect"))
    )
    (net (code "143") (name "unconnected-(U1D-IO,_DIFFIO_B29n-PadY15)") (class "Default")
      (node (ref "U1") (pin "Y15") (pinfunction "IO,_DIFFIO_B29n_Y15") (pintype "bidirectional+no_connect"))
    )
    (net (code "144") (name "unconnected-(U1D-IO,_DIFFIO_B29p-PadY14)") (class "Default")
      (node (ref "U1") (pin "Y14") (pinfunction "IO,_DIFFIO_B29p_Y14") (pintype "bidirectional+no_connect"))
    )
    (net (code "145") (name "unconnected-(U1D-IO,_DIFFIO_B30n,_(DQ2B){slash}(DQ5B){slash}(DQ5B)-PadAB16)") (class "Default")
      (node (ref "U1") (pin "AB16") (pinfunction "IO,_DIFFIO_B30n,_(DQ2B)/(DQ5B)/(DQ5B)_AB16") (pintype "bidirectional+no_connect"))
    )
    (net (code "146") (name "unconnected-(U1D-IO,_DIFFIO_B30p,_(DM2B){slash}(DM5B{slash}BWS#5B){slash}(DM5B{slash}BWS#5B)-PadAA16)") (class "Default")
      (node (ref "U1") (pin "AA16") (pinfunction "IO,_DIFFIO_B30p,_(DM2B)/(DM5B/BWS#5B)/(DM5B/BWS#5B)_AA16") (pintype "bidirectional+no_connect"))
    )
    (net (code "147") (name "unconnected-(U1D-IO,_DIFFIO_B31n-PadW14)") (class "Default")
      (node (ref "U1") (pin "W14") (pinfunction "IO,_DIFFIO_B31n_W14") (pintype "bidirectional+no_connect"))
    )
    (net (code "148") (name "unconnected-(U1D-IO,_DIFFIO_B31p,_(DQS2B{slash}CQ3B,DPCLK5){slash}(DQS2B{slash}CQ3B,DPCLK5){slash}(DQS2B{slash}CQ3B,DPCLK5)-PadV13)") (class "Default")
      (node (ref "U1") (pin "V13") (pinfunction "IO,_DIFFIO_B31p,_(DQS2B/CQ3B,DPCLK5)/(DQS2B/CQ3B,DPCLK5)/(DQS2B/CQ3B,DPCLK5)_V13") (pintype "bidirectional+no_connect"))
    )
    (net (code "149") (name "unconnected-(U1D-IO,_DIFFIO_B32p-PadU13)") (class "Default")
      (node (ref "U1") (pin "U13") (pinfunction "IO,_DIFFIO_B32p_U13") (pintype "bidirectional+no_connect"))
    )
    (net (code "150") (name "unconnected-(U1D-IO,_DIFFIO_B33n-PadU14)") (class "Default")
      (node (ref "U1") (pin "U14") (pinfunction "IO,_DIFFIO_B33n_U14") (pintype "bidirectional+no_connect"))
    )
    (net (code "151") (name "unconnected-(U1D-IO,_DIFFIO_B33p,_(DQ2B){slash}(DQ5B){slash}(DQ5B)-PadV14)") (class "Default")
      (node (ref "U1") (pin "V14") (pinfunction "IO,_DIFFIO_B33p,_(DQ2B)/(DQ5B)/(DQ5B)_V14") (pintype "bidirectional+no_connect"))
    )
    (net (code "152") (name "unconnected-(U1D-IO,_DIFFIO_B34n,_(DQ2B){slash}(DQ5B){slash}(DQ5B)-PadV15)") (class "Default")
      (node (ref "U1") (pin "V15") (pinfunction "IO,_DIFFIO_B34n,_(DQ2B)/(DQ5B)/(DQ5B)_V15") (pintype "bidirectional+no_connect"))
    )
    (net (code "153") (name "unconnected-(U1D-IO,_DIFFIO_B34p-PadU15)") (class "Default")
      (node (ref "U1") (pin "U15") (pinfunction "IO,_DIFFIO_B34p_U15") (pintype "bidirectional+no_connect"))
    )
    (net (code "154") (name "unconnected-(U1D-IO,_DIFFIO_B35p,_(DQ2B){slash}(DQ5B){slash}(DQ5B)-PadW15)") (class "Default")
      (node (ref "U1") (pin "W15") (pinfunction "IO,_DIFFIO_B35p,_(DQ2B)/(DQ5B)/(DQ5B)_W15") (pintype "bidirectional+no_connect"))
    )
    (net (code "155") (name "unconnected-(U1D-IO,_DIFFIO_B36n,_(DQ2B){slash}(DQ5B){slash}(DQ5B)-PadT15)") (class "Default")
      (node (ref "U1") (pin "T15") (pinfunction "IO,_DIFFIO_B36n,_(DQ2B)/(DQ5B)/(DQ5B)_T15") (pintype "bidirectional+no_connect"))
    )
    (net (code "156") (name "unconnected-(U1D-IO,_DIFFIO_B36p-PadT14)") (class "Default")
      (node (ref "U1") (pin "T14") (pinfunction "IO,_DIFFIO_B36p_T14") (pintype "bidirectional+no_connect"))
    )
    (net (code "157") (name "unconnected-(U1D-IO,_DIFFIO_B37n-PadAB17)") (class "Default")
      (node (ref "U1") (pin "AB17") (pinfunction "IO,_DIFFIO_B37n_AB17") (pintype "bidirectional+no_connect"))
    )
    (net (code "158") (name "unconnected-(U1D-IO,_DIFFIO_B37p-PadAA17)") (class "Default")
      (node (ref "U1") (pin "AA17") (pinfunction "IO,_DIFFIO_B37p_AA17") (pintype "bidirectional+no_connect"))
    )
    (net (code "159") (name "unconnected-(U1D-IO,_DIFFIO_B38n,_(DQS0B{slash}CQ1B,CDPCLK3){slash}(DQS0B{slash}CQ1B,CDPCLK3){slash}(DQS0B{slash}CQ1B,CDPCLK3)-PadY17)") (class "Default")
      (node (ref "U1") (pin "Y17") (pinfunction "IO,_DIFFIO_B38n,_(DQS0B/CQ1B,CDPCLK3)/(DQS0B/CQ1B,CDPCLK3)/(DQS0B/CQ1B,CDPCLK3)_Y17") (pintype "bidirectional+no_connect"))
    )
    (net (code "160") (name "unconnected-(U1D-IO,_DIFFIO_B38p,_(DQ2B){slash}(DQ5B){slash}(DQ5B)-PadW17)") (class "Default")
      (node (ref "U1") (pin "W17") (pinfunction "IO,_DIFFIO_B38p,_(DQ2B)/(DQ5B)/(DQ5B)_W17") (pintype "bidirectional+no_connect"))
    )
    (net (code "161") (name "unconnected-(U1D-IO,_DIFFIO_B39n,_(DQ2B){slash}(DQ5B){slash}(DQ5B)-PadAB20)") (class "Default")
      (node (ref "U1") (pin "AB20") (pinfunction "IO,_DIFFIO_B39n,_(DQ2B)/(DQ5B)/(DQ5B)_AB20") (pintype "bidirectional+no_connect"))
    )
    (net (code "162") (name "unconnected-(U1D-IO,_DIFFIO_B39p,__{slash}(DQ5B){slash}(DQ5B)-PadAA20)") (class "Default")
      (node (ref "U1") (pin "AA20") (pinfunction "IO,_DIFFIO_B39p,__/(DQ5B)/(DQ5B)_AA20") (pintype "bidirectional+no_connect"))
    )
    (net (code "163") (name "unconnected-(U1D-IO,_DIFFIO_B40n-PadU17)") (class "Default")
      (node (ref "U1") (pin "U17") (pinfunction "IO,_DIFFIO_B40n_U17") (pintype "bidirectional+no_connect"))
    )
    (net (code "164") (name "unconnected-(U1D-IO,_DIFFIO_B40p-PadU16)") (class "Default")
      (node (ref "U1") (pin "U16") (pinfunction "IO,_DIFFIO_B40p_U16") (pintype "bidirectional+no_connect"))
    )
    (net (code "165") (name "unconnected-(U1D-IO,_DIFFIO_B41n-PadR15)") (class "Default")
      (node (ref "U1") (pin "R15") (pinfunction "IO,_DIFFIO_B41n_R15") (pintype "bidirectional+no_connect"))
    )
    (net (code "166") (name "unconnected-(U1D-IO,_DIFFIO_B41p-PadR14)") (class "Default")
      (node (ref "U1") (pin "R14") (pinfunction "IO,_DIFFIO_B41p_R14") (pintype "bidirectional+no_connect"))
    )
    (net (code "167") (name "unconnected-(U1D-IO,_PLL4_CLKOUTn-PadR16)") (class "Default")
      (node (ref "U1") (pin "R16") (pinfunction "IO,_PLL4_CLKOUTn_R16") (pintype "bidirectional+no_connect"))
    )
    (net (code "168") (name "unconnected-(U1D-IO,_PLL4_CLKOUTp-PadT16)") (class "Default")
      (node (ref "U1") (pin "T16") (pinfunction "IO,_PLL4_CLKOUTp_T16") (pintype "bidirectional+no_connect"))
    )
    (net (code "169") (name "unconnected-(U1D-IO,_RDN2-PadAB19)") (class "Default")
      (node (ref "U1") (pin "AB19") (pinfunction "IO,_RDN2_AB19") (pintype "bidirectional+no_connect"))
    )
    (net (code "170") (name "unconnected-(U1D-IO,_RUP2-PadAA19)") (class "Default")
      (node (ref "U1") (pin "AA19") (pinfunction "IO,_RUP2_AA19") (pintype "bidirectional+no_connect"))
    )
    (net (code "171") (name "unconnected-(U1D-IO,_VREFB4N0-PadAA18)") (class "Default")
      (node (ref "U1") (pin "AA18") (pinfunction "IO,_VREFB4N0_AA18") (pintype "bidirectional+no_connect"))
    )
    (net (code "172") (name "unconnected-(U1D-IO,_VREFB4N1-PadV12)") (class "Default")
      (node (ref "U1") (pin "V12") (pinfunction "IO,_VREFB4N1_V12") (pintype "bidirectional+no_connect"))
    )
    (net (code "173") (name "unconnected-(U1D-IO-PadV16)") (class "Default")
      (node (ref "U1") (pin "V16") (pinfunction "IO_V16") (pintype "bidirectional+no_connect"))
    )
    (net (code "174") (name "unconnected-(U1E-IO,_(DQS3R{slash}CQ3R#,CDPCLK4){slash}(DQS3R{slash}CQ3R#,CDPCLK4){slash}(DQS3R{slash}CQ3R#,CDPCLK4)-PadW20)") (class "Default")
      (node (ref "U1") (pin "W20") (pinfunction "IO,_(DQS3R/CQ3R#,CDPCLK4)/(DQS3R/CQ3R#,CDPCLK4)/(DQS3R/CQ3R#,CDPCLK4)_W20") (pintype "bidirectional+no_connect"))
    )
    (net (code "175") (name "unconnected-(U1E-IO,_DIFFIO_R18n,_(DQ1R){slash}(DQ3R){slash}(DQ1R)-PadM20)") (class "Default")
      (node (ref "U1") (pin "M20") (pinfunction "IO,_DIFFIO_R18n,_(DQ1R)/(DQ3R)/(DQ1R)_M20") (pintype "bidirectional+no_connect"))
    )
    (net (code "176") (name "unconnected-(U1E-IO,_DIFFIO_R18p,_(DQ1R){slash}(DQ3R){slash}(DQ1R)-PadM19)") (class "Default")
      (node (ref "U1") (pin "M19") (pinfunction "IO,_DIFFIO_R18p,_(DQ1R)/(DQ3R)/(DQ1R)_M19") (pintype "bidirectional+no_connect"))
    )
    (net (code "177") (name "unconnected-(U1E-IO,_DIFFIO_R19n,_(DQ1R){slash}(DQ3R){slash}(DQ1R)-PadM22)") (class "Default")
      (node (ref "U1") (pin "M22") (pinfunction "IO,_DIFFIO_R19n,_(DQ1R)/(DQ3R)/(DQ1R)_M22") (pintype "bidirectional+no_connect"))
    )
    (net (code "178") (name "unconnected-(U1E-IO,_DIFFIO_R19p,_(DQ1R){slash}(DQ3R){slash}(DQ1R)-PadM21)") (class "Default")
      (node (ref "U1") (pin "M21") (pinfunction "IO,_DIFFIO_R19p,_(DQ1R)/(DQ3R)/(DQ1R)_M21") (pintype "bidirectional+no_connect"))
    )
    (net (code "179") (name "unconnected-(U1E-IO,_DIFFIO_R20n,_(DEV_OE)-PadN22)") (class "Default")
      (node (ref "U1") (pin "N22") (pinfunction "IO,_DIFFIO_R20n,_(DEV_OE)_N22") (pintype "bidirectional+no_connect"))
    )
    (net (code "180") (name "unconnected-(U1E-IO,_DIFFIO_R20p,_(DEV_CLRn)-PadN21)") (class "Default")
      (node (ref "U1") (pin "N21") (pinfunction "IO,_DIFFIO_R20p,_(DEV_CLRn)_N21") (pintype "bidirectional+no_connect"))
    )
    (net (code "181") (name "unconnected-(U1E-IO,_DIFFIO_R21n-PadN17)") (class "Default")
      (node (ref "U1") (pin "N17") (pinfunction "IO,_DIFFIO_R21n_N17") (pintype "bidirectional+no_connect"))
    )
    (net (code "182") (name "unconnected-(U1E-IO,_DIFFIO_R21p,_(DQS1R{slash}CQ1R#,DPCLK6){slash}(DQS1R{slash}CQ1R#,DPCLK6){slash}(DQS1R{slash}CQ1R#,DPCLK6)-PadN18)") (class "Default")
      (node (ref "U1") (pin "N18") (pinfunction "IO,_DIFFIO_R21p,_(DQS1R/CQ1R#,DPCLK6)/(DQS1R/CQ1R#,DPCLK6)/(DQS1R/CQ1R#,DPCLK6)_N18") (pintype "bidirectional+no_connect"))
    )
    (net (code "183") (name "unconnected-(U1E-IO,_DIFFIO_R22n,_(DQ1R){slash}(DQ3R){slash}(DQ1R)-PadN20)") (class "Default")
      (node (ref "U1") (pin "N20") (pinfunction "IO,_DIFFIO_R22n,_(DQ1R)/(DQ3R)/(DQ1R)_N20") (pintype "bidirectional+no_connect"))
    )
    (net (code "184") (name "unconnected-(U1E-IO,_DIFFIO_R22p-PadN19)") (class "Default")
      (node (ref "U1") (pin "N19") (pinfunction "IO,_DIFFIO_R22p_N19") (pintype "bidirectional+no_connect"))
    )
    (net (code "185") (name "unconnected-(U1E-IO,_DIFFIO_R23n,_(DQ1R){slash}(DQ3R){slash}(DQ1R)-PadP22)") (class "Default")
      (node (ref "U1") (pin "P22") (pinfunction "IO,_DIFFIO_R23n,_(DQ1R)/(DQ3R)/(DQ1R)_P22") (pintype "bidirectional+no_connect"))
    )
    (net (code "186") (name "unconnected-(U1E-IO,_DIFFIO_R23p,_(DQ1R){slash}(DQ3R){slash}(DQ1R)-PadP21)") (class "Default")
      (node (ref "U1") (pin "P21") (pinfunction "IO,_DIFFIO_R23p,_(DQ1R)/(DQ3R)/(DQ1R)_P21") (pintype "bidirectional+no_connect"))
    )
    (net (code "187") (name "unconnected-(U1E-IO,_DIFFIO_R24n,_(DQ1R){slash}(DQ3R){slash}(DQ1R)-PadR22)") (class "Default")
      (node (ref "U1") (pin "R22") (pinfunction "IO,_DIFFIO_R24n,_(DQ1R)/(DQ3R)/(DQ1R)_R22") (pintype "bidirectional+no_connect"))
    )
    (net (code "188") (name "unconnected-(U1E-IO,_DIFFIO_R24p,_(DQ1R){slash}(DQ3R){slash}(DQ1R)-PadR21)") (class "Default")
      (node (ref "U1") (pin "R21") (pinfunction "IO,_DIFFIO_R24p,_(DQ1R)/(DQ3R)/(DQ1R)_R21") (pintype "bidirectional+no_connect"))
    )
    (net (code "189") (name "unconnected-(U1E-IO,_DIFFIO_R25p-PadN16)") (class "Default")
      (node (ref "U1") (pin "N16") (pinfunction "IO,_DIFFIO_R25p_N16") (pintype "bidirectional+no_connect"))
    )
    (net (code "190") (name "unconnected-(U1E-IO,_DIFFIO_R26n-PadR18)") (class "Default")
      (node (ref "U1") (pin "R18") (pinfunction "IO,_DIFFIO_R26n_R18") (pintype "bidirectional+no_connect"))
    )
    (net (code "191") (name "unconnected-(U1E-IO,_DIFFIO_R26p,_(DM1R{slash}BWS#1R){slash}(DM3R{slash}BWS#3R){slash}(DM1R{slash}BWS#1R)-PadR19)") (class "Default")
      (node (ref "U1") (pin "R19") (pinfunction "IO,_DIFFIO_R26p,_(DM1R/BWS#1R)/(DM3R/BWS#3R)/(DM1R/BWS#1R)_R19") (pintype "bidirectional+no_connect"))
    )
    (net (code "192") (name "unconnected-(U1E-IO,_DIFFIO_R27n,_(DQ3R){slash}(DQ3R){slash}(DQ1R)-PadU22)") (class "Default")
      (node (ref "U1") (pin "U22") (pinfunction "IO,_DIFFIO_R27n,_(DQ3R)/(DQ3R)/(DQ1R)_U22") (pintype "bidirectional+no_connect"))
    )
    (net (code "193") (name "unconnected-(U1E-IO,_DIFFIO_R27p,_(DQ3R){slash}(DQ3R){slash}(DQ1R)-PadU21)") (class "Default")
      (node (ref "U1") (pin "U21") (pinfunction "IO,_DIFFIO_R27p,_(DQ3R)/(DQ3R)/(DQ1R)_U21") (pintype "bidirectional+no_connect"))
    )
    (net (code "194") (name "unconnected-(U1E-IO,_DIFFIO_R28n,_(DQ3R){slash}(DQ3R){slash}(DQ1R)-PadR20)") (class "Default")
      (node (ref "U1") (pin "R20") (pinfunction "IO,_DIFFIO_R28n,_(DQ3R)/(DQ3R)/(DQ1R)_R20") (pintype "bidirectional+no_connect"))
    )
    (net (code "195") (name "unconnected-(U1E-IO,_DIFFIO_R29n,_(DQ3R){slash}(DQ3R){slash}(DQ1R)-PadV22)") (class "Default")
      (node (ref "U1") (pin "V22") (pinfunction "IO,_DIFFIO_R29n,_(DQ3R)/(DQ3R)/(DQ1R)_V22") (pintype "bidirectional+no_connect"))
    )
    (net (code "196") (name "unconnected-(U1E-IO,_DIFFIO_R29p,_(DQ3R){slash}(DQ3R){slash}(DQ1R)-PadV21)") (class "Default")
      (node (ref "U1") (pin "V21") (pinfunction "IO,_DIFFIO_R29p,_(DQ3R)/(DQ3R)/(DQ1R)_V21") (pintype "bidirectional+no_connect"))
    )
    (net (code "197") (name "unconnected-(U1E-IO,_DIFFIO_R30n-PadR17)") (class "Default")
      (node (ref "U1") (pin "R17") (pinfunction "IO,_DIFFIO_R30n_R17") (pintype "bidirectional+no_connect"))
    )
    (net (code "198") (name "unconnected-(U1E-IO,_DIFFIO_R30p-PadP17)") (class "Default")
      (node (ref "U1") (pin "P17") (pinfunction "IO,_DIFFIO_R30p_P17") (pintype "bidirectional+no_connect"))
    )
    (net (code "199") (name "unconnected-(U1E-IO,_DIFFIO_R31n-PadT20)") (class "Default")
      (node (ref "U1") (pin "T20") (pinfunction "IO,_DIFFIO_R31n_T20") (pintype "bidirectional+no_connect"))
    )
    (net (code "200") (name "unconnected-(U1E-IO,_DIFFIO_R31p-PadT19)") (class "Default")
      (node (ref "U1") (pin "T19") (pinfunction "IO,_DIFFIO_R31p_T19") (pintype "bidirectional+no_connect"))
    )
    (net (code "201") (name "unconnected-(U1E-IO,_DIFFIO_R32n,_(DQ3R){slash}(DQ3R){slash}(DQ1R)-PadW22)") (class "Default")
      (node (ref "U1") (pin "W22") (pinfunction "IO,_DIFFIO_R32n,_(DQ3R)/(DQ3R)/(DQ1R)_W22") (pintype "bidirectional+no_connect"))
    )
    (net (code "202") (name "unconnected-(U1E-IO,_DIFFIO_R32p,_(DQ3R){slash}(DQ3R){slash}(DQ1R)-PadW21)") (class "Default")
      (node (ref "U1") (pin "W21") (pinfunction "IO,_DIFFIO_R32p,_(DQ3R)/(DQ3R)/(DQ1R)_W21") (pintype "bidirectional+no_connect"))
    )
    (net (code "203") (name "unconnected-(U1E-IO,_DIFFIO_R34n,_(DQ3R){slash}(DQ3R){slash}(DQ1R)-PadU20)") (class "Default")
      (node (ref "U1") (pin "U20") (pinfunction "IO,_DIFFIO_R34n,_(DQ3R)/(DQ3R)/(DQ1R)_U20") (pintype "bidirectional+no_connect"))
    )
    (net (code "204") (name "unconnected-(U1E-IO,_DIFFIO_R34p-PadU19)") (class "Default")
      (node (ref "U1") (pin "U19") (pinfunction "IO,_DIFFIO_R34p_U19") (pintype "bidirectional+no_connect"))
    )
    (net (code "205") (name "unconnected-(U1E-IO,_DIFFIO_R35n,_(DQ3R){slash}(DQ3R){slash}(DQ1R)-PadY22)") (class "Default")
      (node (ref "U1") (pin "Y22") (pinfunction "IO,_DIFFIO_R35n,_(DQ3R)/(DQ3R)/(DQ1R)_Y22") (pintype "bidirectional+no_connect"))
    )
    (net (code "206") (name "unconnected-(U1E-IO,_DIFFIO_R35p-PadY21)") (class "Default")
      (node (ref "U1") (pin "Y21") (pinfunction "IO,_DIFFIO_R35p_Y21") (pintype "bidirectional+no_connect"))
    )
    (net (code "207") (name "unconnected-(U1E-IO,_DIFFIO_R36p,_(DM3R{slash}BWS#3R){slash}(DM3R{slash}BWS#3R){slash}(DM1R{slash}BWS#1R)-PadAA21)") (class "Default")
      (node (ref "U1") (pin "AA21") (pinfunction "IO,_DIFFIO_R36p,_(DM3R/BWS#3R)/(DM3R/BWS#3R)/(DM1R/BWS#1R)_AA21") (pintype "bidirectional+no_connect"))
    )
    (net (code "208") (name "unconnected-(U1E-IO,_RDN3-PadT18)") (class "Default")
      (node (ref "U1") (pin "T18") (pinfunction "IO,_RDN3_T18") (pintype "bidirectional+no_connect"))
    )
    (net (code "209") (name "unconnected-(U1E-IO,_RUP3-PadT17)") (class "Default")
      (node (ref "U1") (pin "T17") (pinfunction "IO,_RUP3_T17") (pintype "bidirectional+no_connect"))
    )
    (net (code "210") (name "unconnected-(U1E-IO,_VREFB5N0-PadP20)") (class "Default")
      (node (ref "U1") (pin "P20") (pinfunction "IO,_VREFB5N0_P20") (pintype "bidirectional+no_connect"))
    )
    (net (code "211") (name "unconnected-(U1E-IO,_VREFB5N1-PadW19)") (class "Default")
      (node (ref "U1") (pin "W19") (pinfunction "IO,_VREFB5N1_W19") (pintype "bidirectional+no_connect"))
    )
    (net (code "212") (name "unconnected-(U1E-IO-PadM16)") (class "Default")
      (node (ref "U1") (pin "M16") (pinfunction "IO_M16") (pintype "bidirectional+no_connect"))
    )
    (net (code "213") (name "unconnected-(U1F-IO,_DIFFIO_R1n,_(DQ2R){slash}(DQ1R){slash}(DQ1R)-PadF17)") (class "Default")
      (node (ref "U1") (pin "F17") (pinfunction "IO,_DIFFIO_R1n,_(DQ2R)/(DQ1R)/(DQ1R)_F17") (pintype "bidirectional+no_connect"))
    )
    (net (code "214") (name "unconnected-(U1F-IO,_DIFFIO_R1p-PadG17)") (class "Default")
      (node (ref "U1") (pin "G17") (pinfunction "IO,_DIFFIO_R1p_G17") (pintype "bidirectional+no_connect"))
    )
    (net (code "215") (name "unconnected-(U1F-IO,_DIFFIO_R2n,_(PADD20),_(DQS2R{slash}CQ3R,CDPCLK5){slash}(DQS2R{slash}CQ3R,CDPCLK5){slash}(DQS2R{slash}CQ3R,CDPCLK5)-PadC20)") (class "Default")
      (node (ref "U1") (pin "C20") (pinfunction "IO,_DIFFIO_R2n,_(PADD20),_(DQS2R/CQ3R,CDPCLK5)/(DQS2R/CQ3R,CDPCLK5)/(DQS2R/CQ3R,CDPCLK5)_C20") (pintype "bidirectional+no_connect"))
    )
    (net (code "216") (name "unconnected-(U1F-IO,_DIFFIO_R2p-PadD20)") (class "Default")
      (node (ref "U1") (pin "D20") (pinfunction "IO,_DIFFIO_R2p_D20") (pintype "bidirectional+no_connect"))
    )
    (net (code "217") (name "unconnected-(U1F-IO,_DIFFIO_R3n,_(PADD22),_(DQ2R){slash}(DQ1R){slash}(DQ1R)-PadB22)") (class "Default")
      (node (ref "U1") (pin "B22") (pinfunction "IO,_DIFFIO_R3n,_(PADD22),_(DQ2R)/(DQ1R)/(DQ1R)_B22") (pintype "bidirectional+no_connect"))
    )
    (net (code "218") (name "unconnected-(U1F-IO,_DIFFIO_R3p,_(PADD21),_(DQ2R){slash}(DQ1R){slash}(DQ1R)-PadB21)") (class "Default")
      (node (ref "U1") (pin "B21") (pinfunction "IO,_DIFFIO_R3p,_(PADD21),_(DQ2R)/(DQ1R)/(DQ1R)_B21") (pintype "bidirectional+no_connect"))
    )
    (net (code "219") (name "unconnected-(U1F-IO,_DIFFIO_R4n,_(DQ2R){slash}(DQ1R){slash}(DQ1R)-PadC22)") (class "Default")
      (node (ref "U1") (pin "C22") (pinfunction "IO,_DIFFIO_R4n,_(DQ2R)/(DQ1R)/(DQ1R)_C22") (pintype "bidirectional+no_connect"))
    )
    (net (code "220") (name "unconnected-(U1F-IO,_DIFFIO_R4p,_(DQ2R){slash}(DQ1R){slash}(DQ1R)-PadC21)") (class "Default")
      (node (ref "U1") (pin "C21") (pinfunction "IO,_DIFFIO_R4p,_(DQ2R)/(DQ1R)/(DQ1R)_C21") (pintype "bidirectional+no_connect"))
    )
    (net (code "221") (name "unconnected-(U1F-IO,_DIFFIO_R5n,_(PADD23),_(DQ2R){slash}(DQ1R){slash}(DQ1R)-PadG18)") (class "Default")
      (node (ref "U1") (pin "G18") (pinfunction "IO,_DIFFIO_R5n,_(PADD23),_(DQ2R)/(DQ1R)/(DQ1R)_G18") (pintype "bidirectional+no_connect"))
    )
    (net (code "222") (name "unconnected-(U1F-IO,_DIFFIO_R5p-PadH17)") (class "Default")
      (node (ref "U1") (pin "H17") (pinfunction "IO,_DIFFIO_R5p_H17") (pintype "bidirectional+no_connect"))
    )
    (net (code "223") (name "unconnected-(U1F-IO,_DIFFIO_R6n,_(nAVD),_(DQ2R){slash}(DQ1R){slash}(DQ1R)-PadF20)") (class "Default")
      (node (ref "U1") (pin "F20") (pinfunction "IO,_DIFFIO_R6n,_(nAVD),_(DQ2R)/(DQ1R)/(DQ1R)_F20") (pintype "bidirectional+no_connect"))
    )
    (net (code "224") (name "unconnected-(U1F-IO,_DIFFIO_R6p,_(DQ2R){slash}(DQ1R){slash}(DQ1R)-PadF19)") (class "Default")
      (node (ref "U1") (pin "F19") (pinfunction "IO,_DIFFIO_R6p,_(DQ2R)/(DQ1R)/(DQ1R)_F19") (pintype "bidirectional+no_connect"))
    )
    (net (code "225") (name "unconnected-(U1F-IO,_DIFFIO_R7n,_(DM2R){slash}(DM1R{slash}BWS#1R){slash}(DM1R{slash}BWS#1R)-PadD22)") (class "Default")
      (node (ref "U1") (pin "D22") (pinfunction "IO,_DIFFIO_R7n,_(DM2R)/(DM1R/BWS#1R)/(DM1R/BWS#1R)_D22") (pintype "bidirectional+no_connect"))
    )
    (net (code "226") (name "unconnected-(U1F-IO,_DIFFIO_R7p,__{slash}(DQ1R){slash}(DQ1R)-PadD21)") (class "Default")
      (node (ref "U1") (pin "D21") (pinfunction "IO,_DIFFIO_R7p,__/(DQ1R)/(DQ1R)_D21") (pintype "bidirectional+no_connect"))
    )
    (net (code "227") (name "unconnected-(U1F-IO,_DIFFIO_R8n,_(nWE),_(DQ0R){slash}(DQ1R){slash}(DQ1R)-PadE22)") (class "Default")
      (node (ref "U1") (pin "E22") (pinfunction "IO,_DIFFIO_R8n,_(nWE),_(DQ0R)/(DQ1R)/(DQ1R)_E22") (pintype "bidirectional+no_connect"))
    )
    (net (code "228") (name "unconnected-(U1F-IO,_DIFFIO_R8p,_(nOE),__{slash}(DQ1R){slash}(DQ1R)-PadE21)") (class "Default")
      (node (ref "U1") (pin "E21") (pinfunction "IO,_DIFFIO_R8p,_(nOE),__/(DQ1R)/(DQ1R)_E21") (pintype "bidirectional+no_connect"))
    )
    (net (code "229") (name "unconnected-(U1F-IO,_DIFFIO_R9n,_(DQ0R){slash}(DQ1R){slash}(DQ1R)-PadH20)") (class "Default")
      (node (ref "U1") (pin "H20") (pinfunction "IO,_DIFFIO_R9n,_(DQ0R)/(DQ1R)/(DQ1R)_H20") (pintype "bidirectional+no_connect"))
    )
    (net (code "230") (name "unconnected-(U1F-IO,_DIFFIO_R9p,_(DQ0R){slash}(DQ1R){slash}(DQ1R)-PadH19)") (class "Default")
      (node (ref "U1") (pin "H19") (pinfunction "IO,_DIFFIO_R9p,_(DQ0R)/(DQ1R)/(DQ1R)_H19") (pintype "bidirectional+no_connect"))
    )
    (net (code "231") (name "unconnected-(U1F-IO,_DIFFIO_R10n-PadJ20)") (class "Default")
      (node (ref "U1") (pin "J20") (pinfunction "IO,_DIFFIO_R10n_J20") (pintype "bidirectional+no_connect"))
    )
    (net (code "232") (name "unconnected-(U1F-IO,_DIFFIO_R10p-PadJ19)") (class "Default")
      (node (ref "U1") (pin "J19") (pinfunction "IO,_DIFFIO_R10p_J19") (pintype "bidirectional+no_connect"))
    )
    (net (code "233") (name "unconnected-(U1F-IO,_DIFFIO_R11n,_(DQ0R){slash}(DQ1R){slash}(DQ1R)-PadF22)") (class "Default")
      (node (ref "U1") (pin "F22") (pinfunction "IO,_DIFFIO_R11n,_(DQ0R)/(DQ1R)/(DQ1R)_F22") (pintype "bidirectional+no_connect"))
    )
    (net (code "234") (name "unconnected-(U1F-IO,_DIFFIO_R11p,_(DQ0R){slash}(DQ1R){slash}(DQ1R)-PadF21)") (class "Default")
      (node (ref "U1") (pin "F21") (pinfunction "IO,_DIFFIO_R11p,_(DQ0R)/(DQ1R)/(DQ1R)_F21") (pintype "bidirectional+no_connect"))
    )
    (net (code "235") (name "unconnected-(U1F-IO,_DIFFIO_R12n-PadJ18)") (class "Default")
      (node (ref "U1") (pin "J18") (pinfunction "IO,_DIFFIO_R12n_J18") (pintype "bidirectional+no_connect"))
    )
    (net (code "236") (name "unconnected-(U1F-IO,_DIFFIO_R13n-PadK17)") (class "Default")
      (node (ref "U1") (pin "K17") (pinfunction "IO,_DIFFIO_R13n_K17") (pintype "bidirectional+no_connect"))
    )
    (net (code "237") (name "unconnected-(U1F-IO,_DIFFIO_R13p,_(DQ0R){slash}(DQ1R){slash}(DQ1R)-PadK18)") (class "Default")
      (node (ref "U1") (pin "K18") (pinfunction "IO,_DIFFIO_R13p,_(DQ0R)/(DQ1R)/(DQ1R)_K18") (pintype "bidirectional+no_connect"))
    )
    (net (code "238") (name "unconnected-(U1F-IO,_DIFFIO_R14n,_(DQ0R){slash}(DQ1R){slash}(DQ1R)-PadH22)") (class "Default")
      (node (ref "U1") (pin "H22") (pinfunction "IO,_DIFFIO_R14n,_(DQ0R)/(DQ1R)/(DQ1R)_H22") (pintype "bidirectional+no_connect"))
    )
    (net (code "239") (name "unconnected-(U1F-IO,_DIFFIO_R14p,_(DQ0R){slash}(DQ1R){slash}(DQ1R)-PadH21)") (class "Default")
      (node (ref "U1") (pin "H21") (pinfunction "IO,_DIFFIO_R14p,_(DQ0R)/(DQ1R)/(DQ1R)_H21") (pintype "bidirectional+no_connect"))
    )
    (net (code "240") (name "unconnected-(U1F-IO,_DIFFIO_R15n,_(DQS0R{slash}CQ1R,DPCLK7){slash}(DQS0R{slash}CQ1R,DPCLK7){slash}(DQS0R{slash}CQ1R,DPCLK7)-PadJ22)") (class "Default")
      (node (ref "U1") (pin "J22") (pinfunction "IO,_DIFFIO_R15n,_(DQS0R/CQ1R,DPCLK7)/(DQS0R/CQ1R,DPCLK7)/(DQS0R/CQ1R,DPCLK7)_J22") (pintype "bidirectional+no_connect"))
    )
    (net (code "241") (name "unconnected-(U1F-IO,_DIFFIO_R15p,_(DM0R){slash}(DM1R{slash}BWS#1R){slash}(DM1R{slash}BWS#1R)-PadJ21)") (class "Default")
      (node (ref "U1") (pin "J21") (pinfunction "IO,_DIFFIO_R15p,_(DM0R)/(DM1R/BWS#1R)/(DM1R/BWS#1R)_J21") (pintype "bidirectional+no_connect"))
    )
    (net (code "242") (name "unconnected-(U1F-IO,_DIFFIO_R16n,_(nCEO)-PadK22)") (class "Default")
      (node (ref "U1") (pin "K22") (pinfunction "IO,_DIFFIO_R16n,_(nCEO)_K22") (pintype "bidirectional+no_connect"))
    )
    (net (code "243") (name "unconnected-(U1F-IO,_DIFFIO_R16p,_(CLKUSR)-PadK21)") (class "Default")
      (node (ref "U1") (pin "K21") (pinfunction "IO,_DIFFIO_R16p,_(CLKUSR)_K21") (pintype "bidirectional+no_connect"))
    )
    (net (code "244") (name "unconnected-(U1F-IO,_DIFFIO_R17n,_(INIT_DONE)-PadL22)") (class "Default")
      (node (ref "U1") (pin "L22") (pinfunction "IO,_DIFFIO_R17n,_(INIT_DONE)_L22") (pintype "bidirectional+no_connect"))
    )
    (net (code "245") (name "unconnected-(U1F-IO,_DIFFIO_R17p,_(CRC_ERROR)-PadL21)") (class "Default")
      (node (ref "U1") (pin "L21") (pinfunction "IO,_DIFFIO_R17p,_(CRC_ERROR)_L21") (pintype "bidirectional+no_connect"))
    )
    (net (code "246") (name "unconnected-(U1F-IO,_VREFB6N0-PadH18)") (class "Default")
      (node (ref "U1") (pin "H18") (pinfunction "IO,_VREFB6N0_H18") (pintype "bidirectional+no_connect"))
    )
    (net (code "247") (name "unconnected-(U1F-IO,_VREFB6N1-PadK19)") (class "Default")
      (node (ref "U1") (pin "K19") (pinfunction "IO,_VREFB6N1_K19") (pintype "bidirectional+no_connect"))
    )
    (net (code "248") (name "unconnected-(U1F-IO-PadH16)") (class "Default")
      (node (ref "U1") (pin "H16") (pinfunction "IO_H16") (pintype "bidirectional+no_connect"))
    )
    (net (code "249") (name "unconnected-(U1F-IO-PadJ17)") (class "Default")
      (node (ref "U1") (pin "J17") (pinfunction "IO_J17") (pintype "bidirectional+no_connect"))
    )
    (net (code "250") (name "unconnected-(U1G-IO,_DIFFIO_T23n,_(PADD13)-PadE11)") (class "Default")
      (node (ref "U1") (pin "E11") (pinfunction "IO,_DIFFIO_T23n,_(PADD13)_E11") (pintype "bidirectional+no_connect"))
    )
    (net (code "251") (name "unconnected-(U1G-IO,_DIFFIO_T23p,_(PADD14),_(DM4T){slash}(DM5T{slash}BWS#5T){slash}(DM5T{slash}BWS#5T)-PadF11)") (class "Default")
      (node (ref "U1") (pin "F11") (pinfunction "IO,_DIFFIO_T23p,_(PADD14),_(DM4T)/(DM5T/BWS#5T)/(DM5T/BWS#5T)_F11") (pintype "bidirectional+no_connect"))
    )
    (net (code "252") (name "unconnected-(U1G-IO,_DIFFIO_T24n,_(PADD11),_(DQ4T){slash}(DQ5T){slash}(DQ5T)-PadA13)") (class "Default")
      (node (ref "U1") (pin "A13") (pinfunction "IO,_DIFFIO_T24n,_(PADD11),_(DQ4T)/(DQ5T)/(DQ5T)_A13") (pintype "bidirectional+no_connect"))
    )
    (net (code "253") (name "unconnected-(U1G-IO,_DIFFIO_T24p,_(PADD12),_(DQS4T{slash}CQ5T,DPCLK9){slash}(DQS4T{slash}CQ5T,DPCLK9){slash}(DQS4T{slash}CQ5T,DPCLK9)-PadB13)") (class "Default")
      (node (ref "U1") (pin "B13") (pinfunction "IO,_DIFFIO_T24p,_(PADD12),_(DQS4T/CQ5T,DPCLK9)/(DQS4T/CQ5T,DPCLK9)/(DQS4T/CQ5T,DPCLK9)_B13") (pintype "bidirectional+no_connect"))
    )
    (net (code "254") (name "unconnected-(U1G-IO,_DIFFIO_T25n,_(PADD9),_(DQ4T){slash}(DQ5T){slash}(DQ5T)-PadA14)") (class "Default")
      (node (ref "U1") (pin "A14") (pinfunction "IO,_DIFFIO_T25n,_(PADD9),_(DQ4T)/(DQ5T)/(DQ5T)_A14") (pintype "bidirectional+no_connect"))
    )
    (net (code "255") (name "unconnected-(U1G-IO,_DIFFIO_T25p,_(PADD10),_(DQ4T){slash}(DQ5T){slash}(DQ5T)-PadB14)") (class "Default")
      (node (ref "U1") (pin "B14") (pinfunction "IO,_DIFFIO_T25p,_(PADD10),_(DQ4T)/(DQ5T)/(DQ5T)_B14") (pintype "bidirectional+no_connect"))
    )
    (net (code "256") (name "unconnected-(U1G-IO,_DIFFIO_T26n,_(PADD7)-PadC13)") (class "Default")
      (node (ref "U1") (pin "C13") (pinfunction "IO,_DIFFIO_T26n,_(PADD7)_C13") (pintype "bidirectional+no_connect"))
    )
    (net (code "257") (name "unconnected-(U1G-IO,_DIFFIO_T26p,_(PADD8),_(DQ4T){slash}(DQ5T){slash}(DQ5T)-PadD13)") (class "Default")
      (node (ref "U1") (pin "D13") (pinfunction "IO,_DIFFIO_T26p,_(PADD8),_(DQ4T)/(DQ5T)/(DQ5T)_D13") (pintype "bidirectional+no_connect"))
    )
    (net (code "258") (name "unconnected-(U1G-IO,_DIFFIO_T27n,_(PADD5),_(DQ4T){slash}(DQ5T){slash}(DQ5T)-PadA15)") (class "Default")
      (node (ref "U1") (pin "A15") (pinfunction "IO,_DIFFIO_T27n,_(PADD5),_(DQ4T)/(DQ5T)/(DQ5T)_A15") (pintype "bidirectional+no_connect"))
    )
    (net (code "259") (name "unconnected-(U1G-IO,_DIFFIO_T27p,_(PADD6),_(DQ4T){slash}(DQ5T){slash}(DQ5T)-PadB15)") (class "Default")
      (node (ref "U1") (pin "B15") (pinfunction "IO,_DIFFIO_T27p,_(PADD6),_(DQ4T)/(DQ5T)/(DQ5T)_B15") (pintype "bidirectional+no_connect"))
    )
    (net (code "260") (name "unconnected-(U1G-IO,_DIFFIO_T28n,_(PADD3),_(DQ4T){slash}(DQ5T){slash}(DQ5T)-PadE14)") (class "Default")
      (node (ref "U1") (pin "E14") (pinfunction "IO,_DIFFIO_T28n,_(PADD3),_(DQ4T)/(DQ5T)/(DQ5T)_E14") (pintype "bidirectional+no_connect"))
    )
    (net (code "261") (name "unconnected-(U1G-IO,_DIFFIO_T28p,_(PADD4),_(DQS2T{slash}CQ3T,DPCLK8){slash}(DQS2T{slash}CQ3T,DPCLK8){slash}(DQS2T{slash}CQ3T,DPCLK8)-PadF13)") (class "Default")
      (node (ref "U1") (pin "F13") (pinfunction "IO,_DIFFIO_T28p,_(PADD4),_(DQS2T/CQ3T,DPCLK8)/(DQS2T/CQ3T,DPCLK8)/(DQS2T/CQ3T,DPCLK8)_F13") (pintype "bidirectional+no_connect"))
    )
    (net (code "262") (name "unconnected-(U1G-IO,_DIFFIO_T30n,_(DM2T){slash}(DM5T{slash}BWS#5T){slash}(DM5T{slash}BWS#5T)-PadA16)") (class "Default")
      (node (ref "U1") (pin "A16") (pinfunction "IO,_DIFFIO_T30n,_(DM2T)/(DM5T/BWS#5T)/(DM5T/BWS#5T)_A16") (pintype "bidirectional+no_connect"))
    )
    (net (code "263") (name "unconnected-(U1G-IO,_DIFFIO_T30p,_(DQ4T){slash}(DQ5T){slash}(DQ5T)-PadB16)") (class "Default")
      (node (ref "U1") (pin "B16") (pinfunction "IO,_DIFFIO_T30p,_(DQ4T)/(DQ5T)/(DQ5T)_B16") (pintype "bidirectional+no_connect"))
    )
    (net (code "264") (name "unconnected-(U1G-IO,_DIFFIO_T31n,_(PADD1),_(DQ2T){slash}(DQ5T){slash}(DQ5T)-PadA17)") (class "Default")
      (node (ref "U1") (pin "A17") (pinfunction "IO,_DIFFIO_T31n,_(PADD1),_(DQ2T)/(DQ5T)/(DQ5T)_A17") (pintype "bidirectional+no_connect"))
    )
    (net (code "265") (name "unconnected-(U1G-IO,_DIFFIO_T31p,_(PADD2),__{slash}(DQ5T){slash}(DQ5T)-PadB17)") (class "Default")
      (node (ref "U1") (pin "B17") (pinfunction "IO,_DIFFIO_T31p,_(PADD2),__/(DQ5T)/(DQ5T)_B17") (pintype "bidirectional+no_connect"))
    )
    (net (code "266") (name "unconnected-(U1G-IO,_DIFFIO_T32n-PadG14)") (class "Default")
      (node (ref "U1") (pin "G14") (pinfunction "IO,_DIFFIO_T32n_G14") (pintype "bidirectional+no_connect"))
    )
    (net (code "267") (name "unconnected-(U1G-IO,_DIFFIO_T32p-PadG13)") (class "Default")
      (node (ref "U1") (pin "G13") (pinfunction "IO,_DIFFIO_T32p_G13") (pintype "bidirectional+no_connect"))
    )
    (net (code "268") (name "unconnected-(U1G-IO,_DIFFIO_T33n-PadD15)") (class "Default")
      (node (ref "U1") (pin "D15") (pinfunction "IO,_DIFFIO_T33n_D15") (pintype "bidirectional+no_connect"))
    )
    (net (code "269") (name "unconnected-(U1G-IO,_DIFFIO_T33p,_(DQ2T){slash}(DQ5T){slash}(DQ5T)-PadE15)") (class "Default")
      (node (ref "U1") (pin "E15") (pinfunction "IO,_DIFFIO_T33p,_(DQ2T)/(DQ5T)/(DQ5T)_E15") (pintype "bidirectional+no_connect"))
    )
    (net (code "270") (name "unconnected-(U1G-IO,_DIFFIO_T34n,_(DQ2T){slash}(DQ5T){slash}(DQ5T)-PadA18)") (class "Default")
      (node (ref "U1") (pin "A18") (pinfunction "IO,_DIFFIO_T34n,_(DQ2T)/(DQ5T)/(DQ5T)_A18") (pintype "bidirectional+no_connect"))
    )
    (net (code "271") (name "unconnected-(U1G-IO,_DIFFIO_T34p,_(PADD0)-PadB18)") (class "Default")
      (node (ref "U1") (pin "B18") (pinfunction "IO,_DIFFIO_T34p,_(PADD0)_B18") (pintype "bidirectional+no_connect"))
    )
    (net (code "272") (name "unconnected-(U1G-IO,_DIFFIO_T35p,_(DQ2T){slash}(DQ5T){slash}(DQ5T)-PadC17)") (class "Default")
      (node (ref "U1") (pin "C17") (pinfunction "IO,_DIFFIO_T35p,_(DQ2T)/(DQ5T)/(DQ5T)_C17") (pintype "bidirectional+no_connect"))
    )
    (net (code "273") (name "unconnected-(U1G-IO,_DIFFIO_T37n,_(DQ2T){slash}(DQ5T){slash}(DQ5T)-PadC19)") (class "Default")
      (node (ref "U1") (pin "C19") (pinfunction "IO,_DIFFIO_T37n,_(DQ2T)/(DQ5T)/(DQ5T)_C19") (pintype "bidirectional+no_connect"))
    )
    (net (code "274") (name "unconnected-(U1G-IO,_DIFFIO_T37p,_(DQ2T){slash}(DQ5T){slash}(DQ5T)-PadD19)") (class "Default")
      (node (ref "U1") (pin "D19") (pinfunction "IO,_DIFFIO_T37p,_(DQ2T)/(DQ5T)/(DQ5T)_D19") (pintype "bidirectional+no_connect"))
    )
    (net (code "275") (name "unconnected-(U1G-IO,_DIFFIO_T39n-PadC18)") (class "Default")
      (node (ref "U1") (pin "C18") (pinfunction "IO,_DIFFIO_T39n_C18") (pintype "bidirectional+no_connect"))
    )
    (net (code "276") (name "unconnected-(U1G-IO,_DIFFIO_T39p-PadD18)") (class "Default")
      (node (ref "U1") (pin "D18") (pinfunction "IO,_DIFFIO_T39p_D18") (pintype "bidirectional+no_connect"))
    )
    (net (code "277") (name "unconnected-(U1G-IO,_DIFFIO_T40n-PadG15)") (class "Default")
      (node (ref "U1") (pin "G15") (pinfunction "IO,_DIFFIO_T40n_G15") (pintype "bidirectional+no_connect"))
    )
    (net (code "278") (name "unconnected-(U1G-IO,_DIFFIO_T40p,_(DQS0T{slash}CQ1T,CDPCLK6){slash}(DQS0T{slash}CQ1T,CDPCLK6){slash}(DQS0T{slash}CQ1T,CDPCLK6)-PadF14)") (class "Default")
      (node (ref "U1") (pin "F14") (pinfunction "IO,_DIFFIO_T40p,_(DQS0T/CQ1T,CDPCLK6)/(DQS0T/CQ1T,CDPCLK6)/(DQS0T/CQ1T,CDPCLK6)_F14") (pintype "bidirectional+no_connect"))
    )
    (net (code "279") (name "unconnected-(U1G-IO,_DIFFIO_T41n,_(DQ2T){slash}(DQ5T){slash}(DQ5T)-PadF15)") (class "Default")
      (node (ref "U1") (pin "F15") (pinfunction "IO,_DIFFIO_T41n,_(DQ2T)/(DQ5T)/(DQ5T)_F15") (pintype "bidirectional+no_connect"))
    )
    (net (code "280") (name "unconnected-(U1G-IO,_DIFFIO_T41p-PadG16)") (class "Default")
      (node (ref "U1") (pin "G16") (pinfunction "IO,_DIFFIO_T41p_G16") (pintype "bidirectional+no_connect"))
    )
    (net (code "281") (name "unconnected-(U1G-IO,_DIFFIO_T42n-PadF16)") (class "Default")
      (node (ref "U1") (pin "F16") (pinfunction "IO,_DIFFIO_T42n_F16") (pintype "bidirectional+no_connect"))
    )
    (net (code "282") (name "unconnected-(U1G-IO,_DIFFIO_T42p,_(DQ2T){slash}(DQ5T){slash}(DQ5T)-PadE16)") (class "Default")
      (node (ref "U1") (pin "E16") (pinfunction "IO,_DIFFIO_T42p,_(DQ2T)/(DQ5T)/(DQ5T)_E16") (pintype "bidirectional+no_connect"))
    )
    (net (code "283") (name "unconnected-(U1G-IO,_PLL2_CLKOUTn-PadA20)") (class "Default")
      (node (ref "U1") (pin "A20") (pinfunction "IO,_PLL2_CLKOUTn_A20") (pintype "bidirectional+no_connect"))
    )
    (net (code "284") (name "unconnected-(U1G-IO,_PLL2_CLKOUTp-PadB20)") (class "Default")
      (node (ref "U1") (pin "B20") (pinfunction "IO,_PLL2_CLKOUTp_B20") (pintype "bidirectional+no_connect"))
    )
    (net (code "285") (name "unconnected-(U1G-IO,_RDN4-PadA19)") (class "Default")
      (node (ref "U1") (pin "A19") (pinfunction "IO,_RDN4_A19") (pintype "bidirectional+no_connect"))
    )
    (net (code "286") (name "unconnected-(U1G-IO,_RUP4-PadB19)") (class "Default")
      (node (ref "U1") (pin "B19") (pinfunction "IO,_RUP4_B19") (pintype "bidirectional+no_connect"))
    )
    (net (code "287") (name "unconnected-(U1G-IO,_VREFB7N0-PadD17)") (class "Default")
      (node (ref "U1") (pin "D17") (pinfunction "IO,_VREFB7N0_D17") (pintype "bidirectional+no_connect"))
    )
    (net (code "288") (name "unconnected-(U1G-IO,_VREFB7N1-PadC15)") (class "Default")
      (node (ref "U1") (pin "C15") (pinfunction "IO,_VREFB7N1_C15") (pintype "bidirectional+no_connect"))
    )
    (net (code "289") (name "unconnected-(U1G-IO,__{slash}(DQ5T){slash}(DQ5T)-PadE12)") (class "Default")
      (node (ref "U1") (pin "E12") (pinfunction "IO,__/(DQ5T)/(DQ5T)_E12") (pintype "bidirectional+no_connect"))
    )
    (net (code "290") (name "unconnected-(U1G-IO-PadE13)") (class "Default")
      (node (ref "U1") (pin "E13") (pinfunction "IO_E13") (pintype "bidirectional+no_connect"))
    )
    (net (code "291") (name "unconnected-(U1H-IO,_DIFFIO_T1n-PadG9)") (class "Default")
      (node (ref "U1") (pin "G9") (pinfunction "IO,_DIFFIO_T1n_G9") (pintype "bidirectional+no_connect"))
    )
    (net (code "292") (name "unconnected-(U1H-IO,_DIFFIO_T2n,_(DM3T{slash}BWS#3T){slash}(DM3T{slash}BWS#3T){slash}(DM5T{slash}BWS#5T)-PadF7)") (class "Default")
      (node (ref "U1") (pin "F7") (pinfunction "IO,_DIFFIO_T2n,_(DM3T/BWS#3T)/(DM3T/BWS#3T)/(DM5T/BWS#5T)_F7") (pintype "bidirectional+no_connect"))
    )
    (net (code "293") (name "unconnected-(U1H-IO,_DIFFIO_T2p-PadG7)") (class "Default")
      (node (ref "U1") (pin "G7") (pinfunction "IO,_DIFFIO_T2p_G7") (pintype "bidirectional+no_connect"))
    )
    (net (code "294") (name "unconnected-(U1H-IO,_DIFFIO_T3n,_(DQ3T){slash}(DQ3T){slash}(DQ5T)-PadC3)") (class "Default")
      (node (ref "U1") (pin "C3") (pinfunction "IO,_DIFFIO_T3n,_(DQ3T)/(DQ3T)/(DQ5T)_C3") (pintype "bidirectional+no_connect"))
    )
    (net (code "295") (name "unconnected-(U1H-IO,_DIFFIO_T3p,_(DATA12),_(DQS1T{slash}CQ1T#,CDPCLK7){slash}(DQS1T{slash}CQ1T#,CDPCLK7){slash}(DQS1T{slash}CQ1T#,CDPCLK7)-PadC4)") (class "Default")
      (node (ref "U1") (pin "C4") (pinfunction "IO,_DIFFIO_T3p,_(DATA12),_(DQS1T/CQ1T#,CDPCLK7)/(DQS1T/CQ1T#,CDPCLK7)/(DQS1T/CQ1T#,CDPCLK7)_C4") (pintype "bidirectional+no_connect"))
    )
    (net (code "296") (name "unconnected-(U1H-IO,_DIFFIO_T4n-PadD6)") (class "Default")
      (node (ref "U1") (pin "D6") (pinfunction "IO,_DIFFIO_T4n_D6") (pintype "bidirectional+no_connect"))
    )
    (net (code "297") (name "unconnected-(U1H-IO,_DIFFIO_T4p-PadE7)") (class "Default")
      (node (ref "U1") (pin "E7") (pinfunction "IO,_DIFFIO_T4p_E7") (pintype "bidirectional+no_connect"))
    )
    (net (code "298") (name "unconnected-(U1H-IO,_DIFFIO_T5n,_(DATA10),_(DQ3T){slash}(DQ3T){slash}(DQ5T)-PadA3)") (class "Default")
      (node (ref "U1") (pin "A3") (pinfunction "IO,_DIFFIO_T5n,_(DATA10),_(DQ3T)/(DQ3T)/(DQ5T)_A3") (pintype "bidirectional+no_connect"))
    )
    (net (code "299") (name "unconnected-(U1H-IO,_DIFFIO_T5p,_(DATA11),_(DQ3T){slash}(DQ3T){slash}(DQ5T)-PadB3)") (class "Default")
      (node (ref "U1") (pin "B3") (pinfunction "IO,_DIFFIO_T5p,_(DATA11),_(DQ3T)/(DQ3T)/(DQ5T)_B3") (pintype "bidirectional+no_connect"))
    )
    (net (code "300") (name "unconnected-(U1H-IO,_DIFFIO_T7n,_(DATA9),_(DQ3T){slash}(DQ3T){slash}(DQ5T)-PadF8)") (class "Default")
      (node (ref "U1") (pin "F8") (pinfunction "IO,_DIFFIO_T7n,_(DATA9),_(DQ3T)/(DQ3T)/(DQ5T)_F8") (pintype "bidirectional+no_connect"))
    )
    (net (code "301") (name "unconnected-(U1H-IO,_DIFFIO_T7p-PadG8)") (class "Default")
      (node (ref "U1") (pin "G8") (pinfunction "IO,_DIFFIO_T7p_G8") (pintype "bidirectional+no_connect"))
    )
    (net (code "302") (name "unconnected-(U1H-IO,_DIFFIO_T8n,_(DQ3T){slash}(DQ3T){slash}(DQ5T)-PadA4)") (class "Default")
      (node (ref "U1") (pin "A4") (pinfunction "IO,_DIFFIO_T8n,_(DQ3T)/(DQ3T)/(DQ5T)_A4") (pintype "bidirectional+no_connect"))
    )
    (net (code "303") (name "unconnected-(U1H-IO,_DIFFIO_T8p,_(DATA8),_(DQ3T){slash}(DQ3T){slash}(DQ5T)-PadB4)") (class "Default")
      (node (ref "U1") (pin "B4") (pinfunction "IO,_DIFFIO_T8p,_(DATA8),_(DQ3T)/(DQ3T)/(DQ5T)_B4") (pintype "bidirectional+no_connect"))
    )
    (net (code "304") (name "unconnected-(U1H-IO,_DIFFIO_T9n,_(DATA7),_(DQ3T){slash}(DQ3T){slash}(DQ5T)-PadC6)") (class "Default")
      (node (ref "U1") (pin "C6") (pinfunction "IO,_DIFFIO_T9n,_(DATA7),_(DQ3T)/(DQ3T)/(DQ5T)_C6") (pintype "bidirectional+no_connect"))
    )
    (net (code "305") (name "unconnected-(U1H-IO,_DIFFIO_T9p-PadD7)") (class "Default")
      (node (ref "U1") (pin "D7") (pinfunction "IO,_DIFFIO_T9p_D7") (pintype "bidirectional+no_connect"))
    )
    (net (code "306") (name "unconnected-(U1H-IO,_DIFFIO_T10n-PadG10)") (class "Default")
      (node (ref "U1") (pin "G10") (pinfunction "IO,_DIFFIO_T10n_G10") (pintype "bidirectional+no_connect"))
    )
    (net (code "307") (name "unconnected-(U1H-IO,_DIFFIO_T10p,_(DATA6),_(DQ3T){slash}(DQ3T){slash}(DQ5T)-PadF10)") (class "Default")
      (node (ref "U1") (pin "F10") (pinfunction "IO,_DIFFIO_T10p,_(DATA6),_(DQ3T)/(DQ3T)/(DQ5T)_F10") (pintype "bidirectional+no_connect"))
    )
    (net (code "308") (name "unconnected-(U1H-IO,_DIFFIO_T11p,_(DATA5),_(DQ3T){slash}(DQ3T){slash}(DQ5T)-PadA5)") (class "Default")
      (node (ref "U1") (pin "A5") (pinfunction "IO,_DIFFIO_T11p,_(DATA5),_(DQ3T)/(DQ3T)/(DQ5T)_A5") (pintype "bidirectional+no_connect"))
    )
    (net (code "309") (name "unconnected-(U1H-IO,_DIFFIO_T12n-PadD8)") (class "Default")
      (node (ref "U1") (pin "D8") (pinfunction "IO,_DIFFIO_T12n_D8") (pintype "bidirectional+no_connect"))
    )
    (net (code "310") (name "unconnected-(U1H-IO,_DIFFIO_T12p-PadE8)") (class "Default")
      (node (ref "U1") (pin "E8") (pinfunction "IO,_DIFFIO_T12p_E8") (pintype "bidirectional+no_connect"))
    )
    (net (code "311") (name "unconnected-(U1H-IO,_DIFFIO_T13n,_(DATA14),_(DQS3T{slash}CQ3T#,DPCLK11){slash}(DQS3T{slash}CQ3T#,DPCLK11){slash}(DQS3T{slash}CQ3T#,DPCLK11)-PadC8)") (class "Default")
      (node (ref "U1") (pin "C8") (pinfunction "IO,_DIFFIO_T13n,_(DATA14),_(DQS3T/CQ3T#,DPCLK11)/(DQS3T/CQ3T#,DPCLK11)/(DQS3T/CQ3T#,DPCLK11)_C8") (pintype "bidirectional+no_connect"))
    )
    (net (code "312") (name "unconnected-(U1H-IO,_DIFFIO_T13p,_(DATA13),_(DM5T{slash}BWS#5T){slash}(DM3T{slash}BWS#3T){slash}(DM5T{slash}BWS#5T)-PadC7)") (class "Default")
      (node (ref "U1") (pin "C7") (pinfunction "IO,_DIFFIO_T13p,_(DATA13),_(DM5T/BWS#5T)/(DM3T/BWS#3T)/(DM5T/BWS#5T)_C7") (pintype "bidirectional+no_connect"))
    )
    (net (code "313") (name "unconnected-(U1H-IO,_DIFFIO_T14n-PadE9)") (class "Default")
      (node (ref "U1") (pin "E9") (pinfunction "IO,_DIFFIO_T14n_E9") (pintype "bidirectional+no_connect"))
    )
    (net (code "314") (name "unconnected-(U1H-IO,_DIFFIO_T15n,_(PADD19),_(DQ5T){slash}(DQ3T){slash}(DQ5T)-PadA6)") (class "Default")
      (node (ref "U1") (pin "A6") (pinfunction "IO,_DIFFIO_T15n,_(PADD19),_(DQ5T)/(DQ3T)/(DQ5T)_A6") (pintype "bidirectional+no_connect"))
    )
    (net (code "315") (name "unconnected-(U1H-IO,_DIFFIO_T15p,_(DATA15),_(DQ5T){slash}(DQ3T){slash}(DQ5T)-PadB6)") (class "Default")
      (node (ref "U1") (pin "B6") (pinfunction "IO,_DIFFIO_T15p,_(DATA15),_(DQ5T)/(DQ3T)/(DQ5T)_B6") (pintype "bidirectional+no_connect"))
    )
    (net (code "316") (name "unconnected-(U1H-IO,_DIFFIO_T16n,_(PADD18),_(DQ5T){slash}(DQ3T){slash}(DQ5T)-PadA7)") (class "Default")
      (node (ref "U1") (pin "A7") (pinfunction "IO,_DIFFIO_T16n,_(PADD18),_(DQ5T)/(DQ3T)/(DQ5T)_A7") (pintype "bidirectional+no_connect"))
    )
    (net (code "317") (name "unconnected-(U1H-IO,_DIFFIO_T16p,_(DATA4),_(DQ5T){slash}(DQ3T){slash}(DQ5T)-PadB7)") (class "Default")
      (node (ref "U1") (pin "B7") (pinfunction "IO,_DIFFIO_T16p,_(DATA4),_(DQ5T)/(DQ3T)/(DQ5T)_B7") (pintype "bidirectional+no_connect"))
    )
    (net (code "318") (name "unconnected-(U1H-IO,_DIFFIO_T17n,_(DATA2),_(DQ5T){slash}(DQ3T){slash}(DQ5T)-PadA8)") (class "Default")
      (node (ref "U1") (pin "A8") (pinfunction "IO,_DIFFIO_T17n,_(DATA2),_(DQ5T)/(DQ3T)/(DQ5T)_A8") (pintype "bidirectional+no_connect"))
    )
    (net (code "319") (name "unconnected-(U1H-IO,_DIFFIO_T17p,_(DATA3),_(DQ5T){slash}(DQ3T){slash}(DQ5T)-PadB8)") (class "Default")
      (node (ref "U1") (pin "B8") (pinfunction "IO,_DIFFIO_T17p,_(DATA3),_(DQ5T)/(DQ3T)/(DQ5T)_B8") (pintype "bidirectional+no_connect"))
    )
    (net (code "320") (name "unconnected-(U1H-IO,_DIFFIO_T18n-PadG11)") (class "Default")
      (node (ref "U1") (pin "G11") (pinfunction "IO,_DIFFIO_T18n_G11") (pintype "bidirectional+no_connect"))
    )
    (net (code "321") (name "unconnected-(U1H-IO,_DIFFIO_T20n,_(PADD16),_(DQ5T){slash}(DQ3T){slash}(DQ5T)-PadA9)") (class "Default")
      (node (ref "U1") (pin "A9") (pinfunction "IO,_DIFFIO_T20n,_(PADD16),_(DQ5T)/(DQ3T)/(DQ5T)_A9") (pintype "bidirectional+no_connect"))
    )
    (net (code "322") (name "unconnected-(U1H-IO,_DIFFIO_T20p,_(PADD17),_(DQS5T{slash}CQ5T#,DPCLK10){slash}(DQS5T{slash}CQ5T#,DPCLK10){slash}(DQS5T{slash}CQ5T#,DPCLK10)-PadB9)") (class "Default")
      (node (ref "U1") (pin "B9") (pinfunction "IO,_DIFFIO_T20p,_(PADD17),_(DQS5T/CQ5T#,DPCLK10)/(DQS5T/CQ5T#,DPCLK10)/(DQS5T/CQ5T#,DPCLK10)_B9") (pintype "bidirectional+no_connect"))
    )
    (net (code "323") (name "unconnected-(U1H-IO,_DIFFIO_T21n,_(DQ5T){slash}(DQ3T){slash}(DQ5T)-PadA10)") (class "Default")
      (node (ref "U1") (pin "A10") (pinfunction "IO,_DIFFIO_T21n,_(DQ5T)/(DQ3T)/(DQ5T)_A10") (pintype "bidirectional+no_connect"))
    )
    (net (code "324") (name "unconnected-(U1H-IO,_DIFFIO_T21p,_(PADD15)-PadB10)") (class "Default")
      (node (ref "U1") (pin "B10") (pinfunction "IO,_DIFFIO_T21p,_(PADD15)_B10") (pintype "bidirectional+no_connect"))
    )
    (net (code "325") (name "unconnected-(U1H-IO,_DIFFIO_T22n,_(DQ5T){slash}(DQ3T){slash}(DQ5T)-PadD10)") (class "Default")
      (node (ref "U1") (pin "D10") (pinfunction "IO,_DIFFIO_T22n,_(DQ5T)/(DQ3T)/(DQ5T)_D10") (pintype "bidirectional+no_connect"))
    )
    (net (code "326") (name "unconnected-(U1H-IO,_DIFFIO_T22p-PadE10)") (class "Default")
      (node (ref "U1") (pin "E10") (pinfunction "IO,_DIFFIO_T22p_E10") (pintype "bidirectional+no_connect"))
    )
    (net (code "327") (name "unconnected-(U1H-IO,_PLL3_CLKOUTn-PadE6)") (class "Default")
      (node (ref "U1") (pin "E6") (pinfunction "IO,_PLL3_CLKOUTn_E6") (pintype "bidirectional+no_connect"))
    )
    (net (code "328") (name "unconnected-(U1H-IO,_PLL3_CLKOUTp-PadE5)") (class "Default")
      (node (ref "U1") (pin "E5") (pinfunction "IO,_PLL3_CLKOUTp_E5") (pintype "bidirectional+no_connect"))
    )
    (net (code "329") (name "unconnected-(U1H-IO,_VREFB8N0-PadC10)") (class "Default")
      (node (ref "U1") (pin "C10") (pinfunction "IO,_VREFB8N0_C10") (pintype "bidirectional+no_connect"))
    )
    (net (code "330") (name "unconnected-(U1H-IO,_VREFB8N1-PadB5)") (class "Default")
      (node (ref "U1") (pin "B5") (pinfunction "IO,_VREFB8N1_B5") (pintype "bidirectional+no_connect"))
    )
    (net (code "331") (name "unconnected-(U1H-IO-PadF9)") (class "Default")
      (node (ref "U1") (pin "F9") (pinfunction "IO_F9") (pintype "bidirectional+no_connect"))
    )
    (net (code "332") (name "unconnected-(U1I-CLK2,_DIFFCLK_1p-PadT2)") (class "Default")
      (node (ref "U1") (pin "T2") (pinfunction "CLK2,_DIFFCLK_1p_T2") (pintype "input+no_connect"))
    )
    (net (code "333") (name "unconnected-(U1I-CLK3,_DIFFCLK_1n-PadT1)") (class "Default")
      (node (ref "U1") (pin "T1") (pinfunction "CLK3,_DIFFCLK_1n_T1") (pintype "input+no_connect"))
    )
    (net (code "334") (name "unconnected-(U1I-CLK4,_DIFFCLK_2p-PadG21)") (class "Default")
      (node (ref "U1") (pin "G21") (pinfunction "CLK4,_DIFFCLK_2p_G21") (pintype "input+no_connect"))
    )
    (net (code "335") (name "unconnected-(U1I-CLK5,_DIFFCLK_2n-PadG22)") (class "Default")
      (node (ref "U1") (pin "G22") (pinfunction "CLK5,_DIFFCLK_2n_G22") (pintype "input+no_connect"))
    )
    (net (code "336") (name "unconnected-(U1I-CLK6,_DIFFCLK_3p-PadT21)") (class "Default")
      (node (ref "U1") (pin "T21") (pinfunction "CLK6,_DIFFCLK_3p_T21") (pintype "input+no_connect"))
    )
    (net (code "337") (name "unconnected-(U1I-CLK7,_DIFFCLK_3n-PadT22)") (class "Default")
      (node (ref "U1") (pin "T22") (pinfunction "CLK7,_DIFFCLK_3n_T22") (pintype "input+no_connect"))
    )
    (net (code "338") (name "unconnected-(U1I-CLK8,_DIFFCLK_5n-PadA12)") (class "Default")
      (node (ref "U1") (pin "A12") (pinfunction "CLK8,_DIFFCLK_5n_A12") (pintype "input+no_connect"))
    )
    (net (code "339") (name "unconnected-(U1I-CLK9,_DIFFCLK_5p-PadB12)") (class "Default")
      (node (ref "U1") (pin "B12") (pinfunction "CLK9,_DIFFCLK_5p_B12") (pintype "input+no_connect"))
    )
    (net (code "340") (name "unconnected-(U1I-CLK10,_DIFFCLK_4n-PadA11)") (class "Default")
      (node (ref "U1") (pin "A11") (pinfunction "CLK10,_DIFFCLK_4n_A11") (pintype "input+no_connect"))
    )
    (net (code "341") (name "unconnected-(U1I-CLK11,_DIFFCLK_4p-PadB11)") (class "Default")
      (node (ref "U1") (pin "B11") (pinfunction "CLK11,_DIFFCLK_4p_B11") (pintype "input+no_connect"))
    )
    (net (code "342") (name "unconnected-(U1I-CLK12,_DIFFCLK_7n-PadAB12)") (class "Default")
      (node (ref "U1") (pin "AB12") (pinfunction "CLK12,_DIFFCLK_7n_AB12") (pintype "input+no_connect"))
    )
    (net (code "343") (name "unconnected-(U1I-CLK13,_DIFFCLK_7p-PadAA12)") (class "Default")
      (node (ref "U1") (pin "AA12") (pinfunction "CLK13,_DIFFCLK_7p_AA12") (pintype "input+no_connect"))
    )
    (net (code "344") (name "unconnected-(U1I-CLK14,_DIFFCLK_6n-PadAB11)") (class "Default")
      (node (ref "U1") (pin "AB11") (pinfunction "CLK14,_DIFFCLK_6n_AB11") (pintype "input+no_connect"))
    )
    (net (code "345") (name "unconnected-(U1I-CLK15,_DIFFCLK_6p-PadAA11)") (class "Default")
      (node (ref "U1") (pin "AA11") (pinfunction "CLK15,_DIFFCLK_6p_AA11") (pintype "input+no_connect"))
    )
    (net (code "346") (name "unconnected-(U1K-VCCIO2-PadN4)") (class "Default")
      (node (ref "U1") (pin "N4") (pinfunction "VCCIO2_N4") (pintype "power_in+no_connect"))
    )
    (net (code "347") (name "unconnected-(U1K-VCCIO2-PadU4)") (class "Default")
      (node (ref "U1") (pin "U4") (pinfunction "VCCIO2_U4") (pintype "power_in+no_connect"))
    )
    (net (code "348") (name "unconnected-(U1K-VCCIO2-PadW4)") (class "Default")
      (node (ref "U1") (pin "W4") (pinfunction "VCCIO2_W4") (pintype "power_in+no_connect"))
    )
    (net (code "349") (name "unconnected-(U1K-VCCIO3-PadAB2)") (class "Default")
      (node (ref "U1") (pin "AB2") (pinfunction "VCCIO3_AB2") (pintype "power_in+no_connect"))
    )
    (net (code "350") (name "unconnected-(U1K-VCCIO3-PadW5)") (class "Default")
      (node (ref "U1") (pin "W5") (pinfunction "VCCIO3_W5") (pintype "power_in+no_connect"))
    )
    (net (code "351") (name "unconnected-(U1K-VCCIO3-PadW9)") (class "Default")
      (node (ref "U1") (pin "W9") (pinfunction "VCCIO3_W9") (pintype "power_in+no_connect"))
    )
    (net (code "352") (name "unconnected-(U1K-VCCIO3-PadW11)") (class "Default")
      (node (ref "U1") (pin "W11") (pinfunction "VCCIO3_W11") (pintype "power_in+no_connect"))
    )
    (net (code "353") (name "unconnected-(U1K-VCCIO4-PadAB21)") (class "Default")
      (node (ref "U1") (pin "AB21") (pinfunction "VCCIO4_AB21") (pintype "power_in+no_connect"))
    )
    (net (code "354") (name "unconnected-(U1K-VCCIO4-PadW12)") (class "Default")
      (node (ref "U1") (pin "W12") (pinfunction "VCCIO4_W12") (pintype "power_in+no_connect"))
    )
    (net (code "355") (name "unconnected-(U1K-VCCIO4-PadW16)") (class "Default")
      (node (ref "U1") (pin "W16") (pinfunction "VCCIO4_W16") (pintype "power_in+no_connect"))
    )
    (net (code "356") (name "unconnected-(U1K-VCCIO4-PadW18)") (class "Default")
      (node (ref "U1") (pin "W18") (pinfunction "VCCIO4_W18") (pintype "power_in+no_connect"))
    )
    (net (code "357") (name "unconnected-(U1K-VCCIO5-PadP18)") (class "Default")
      (node (ref "U1") (pin "P18") (pinfunction "VCCIO5_P18") (pintype "power_in+no_connect"))
    )
    (net (code "358") (name "unconnected-(U1K-VCCIO5-PadV19)") (class "Default")
      (node (ref "U1") (pin "V19") (pinfunction "VCCIO5_V19") (pintype "power_in+no_connect"))
    )
    (net (code "359") (name "unconnected-(U1K-VCCIO5-PadY19)") (class "Default")
      (node (ref "U1") (pin "Y19") (pinfunction "VCCIO5_Y19") (pintype "power_in+no_connect"))
    )
    (net (code "360") (name "unconnected-(U1K-VCCIO6-PadE19)") (class "Default")
      (node (ref "U1") (pin "E19") (pinfunction "VCCIO6_E19") (pintype "power_in+no_connect"))
    )
    (net (code "361") (name "unconnected-(U1K-VCCIO6-PadG19)") (class "Default")
      (node (ref "U1") (pin "G19") (pinfunction "VCCIO6_G19") (pintype "power_in+no_connect"))
    )
    (net (code "362") (name "unconnected-(U1K-VCCIO6-PadL19)") (class "Default")
      (node (ref "U1") (pin "L19") (pinfunction "VCCIO6_L19") (pintype "power_in+no_connect"))
    )
    (net (code "363") (name "unconnected-(U1K-VCCIO7-PadA21)") (class "Default")
      (node (ref "U1") (pin "A21") (pinfunction "VCCIO7_A21") (pintype "power_in+no_connect"))
    )
    (net (code "364") (name "unconnected-(U1K-VCCIO7-PadD12)") (class "Default")
      (node (ref "U1") (pin "D12") (pinfunction "VCCIO7_D12") (pintype "power_in+no_connect"))
    )
    (net (code "365") (name "unconnected-(U1K-VCCIO7-PadD14)") (class "Default")
      (node (ref "U1") (pin "D14") (pinfunction "VCCIO7_D14") (pintype "power_in+no_connect"))
    )
    (net (code "366") (name "unconnected-(U1K-VCCIO7-PadD16)") (class "Default")
      (node (ref "U1") (pin "D16") (pinfunction "VCCIO7_D16") (pintype "power_in+no_connect"))
    )
    (net (code "367") (name "unconnected-(U1K-VCCIO8-PadA2)") (class "Default")
      (node (ref "U1") (pin "A2") (pinfunction "VCCIO8_A2") (pintype "power_in+no_connect"))
    )
    (net (code "368") (name "unconnected-(U1K-VCCIO8-PadD5)") (class "Default")
      (node (ref "U1") (pin "D5") (pinfunction "VCCIO8_D5") (pintype "power_in+no_connect"))
    )
    (net (code "369") (name "unconnected-(U1K-VCCIO8-PadD9)") (class "Default")
      (node (ref "U1") (pin "D9") (pinfunction "VCCIO8_D9") (pintype "power_in+no_connect"))
    )
    (net (code "370") (name "unconnected-(U1K-VCCIO8-PadD11)") (class "Default")
      (node (ref "U1") (pin "D11") (pinfunction "VCCIO8_D11") (pintype "power_in+no_connect"))
    )
  )
)
